# soap-disp-20210413.net
KiCad netlist of a schematic drawn in EasyEDA
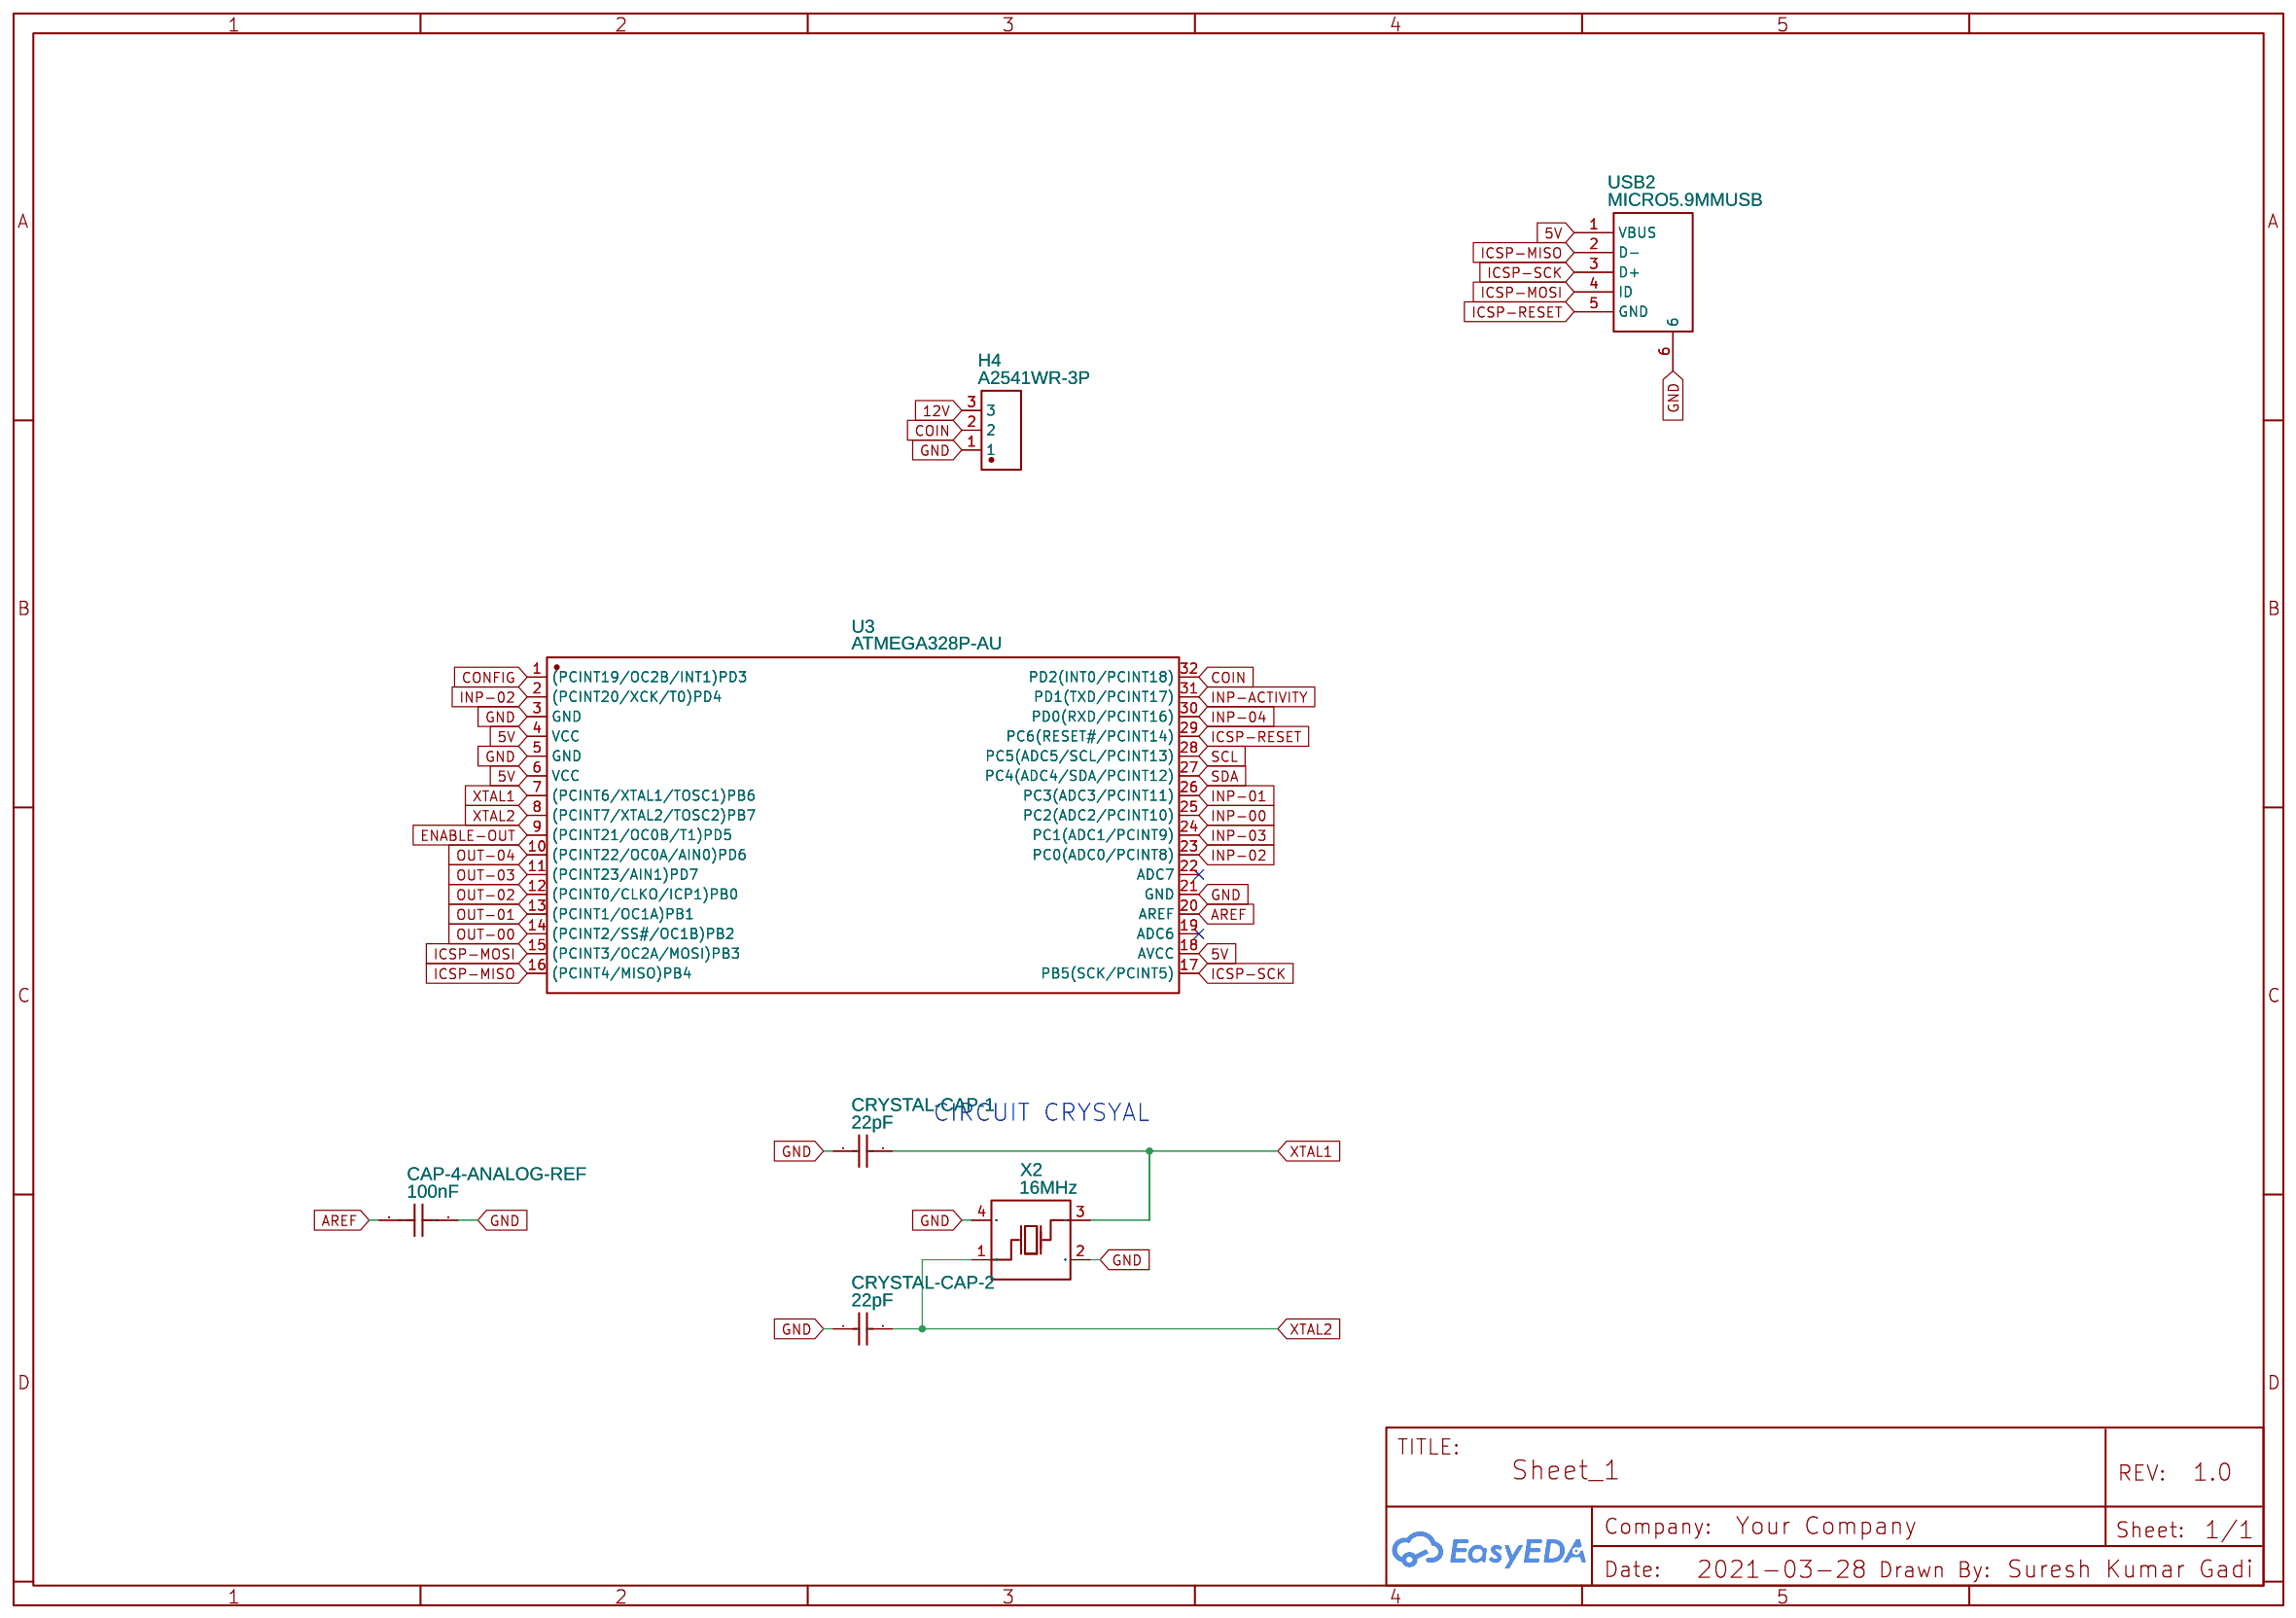
[diagram p0: Computer]
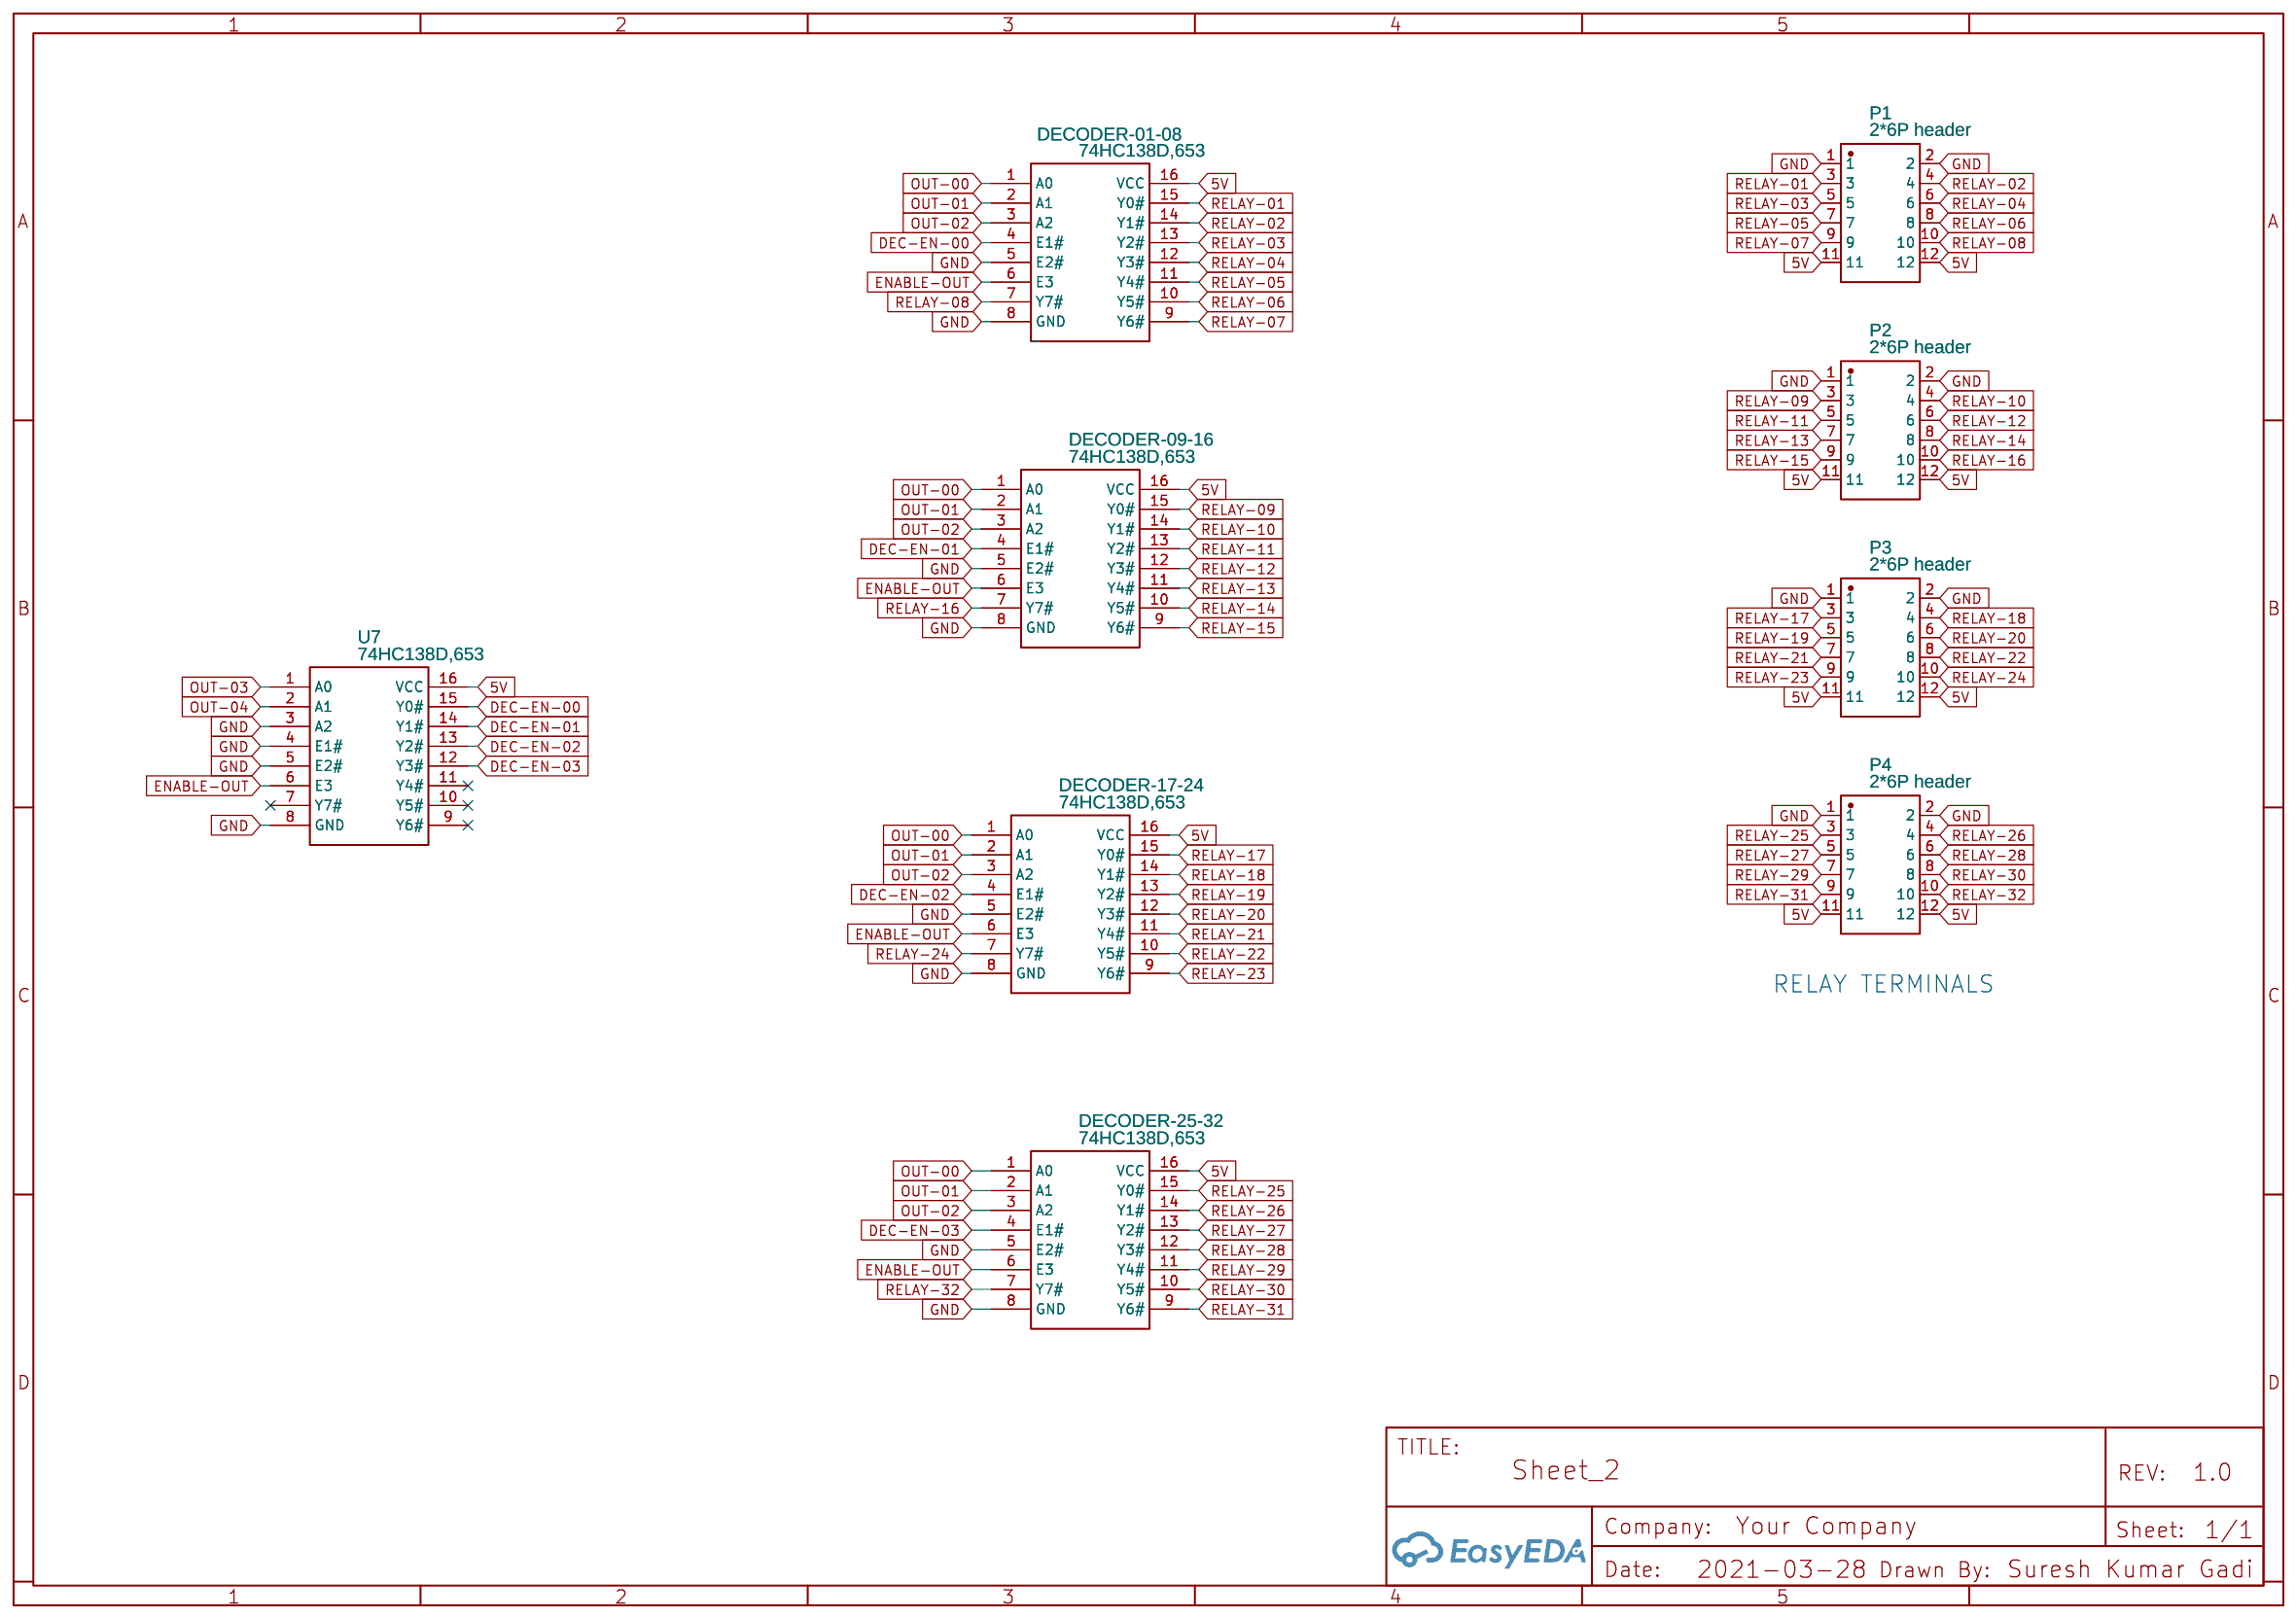
[diagram p1: Relays]
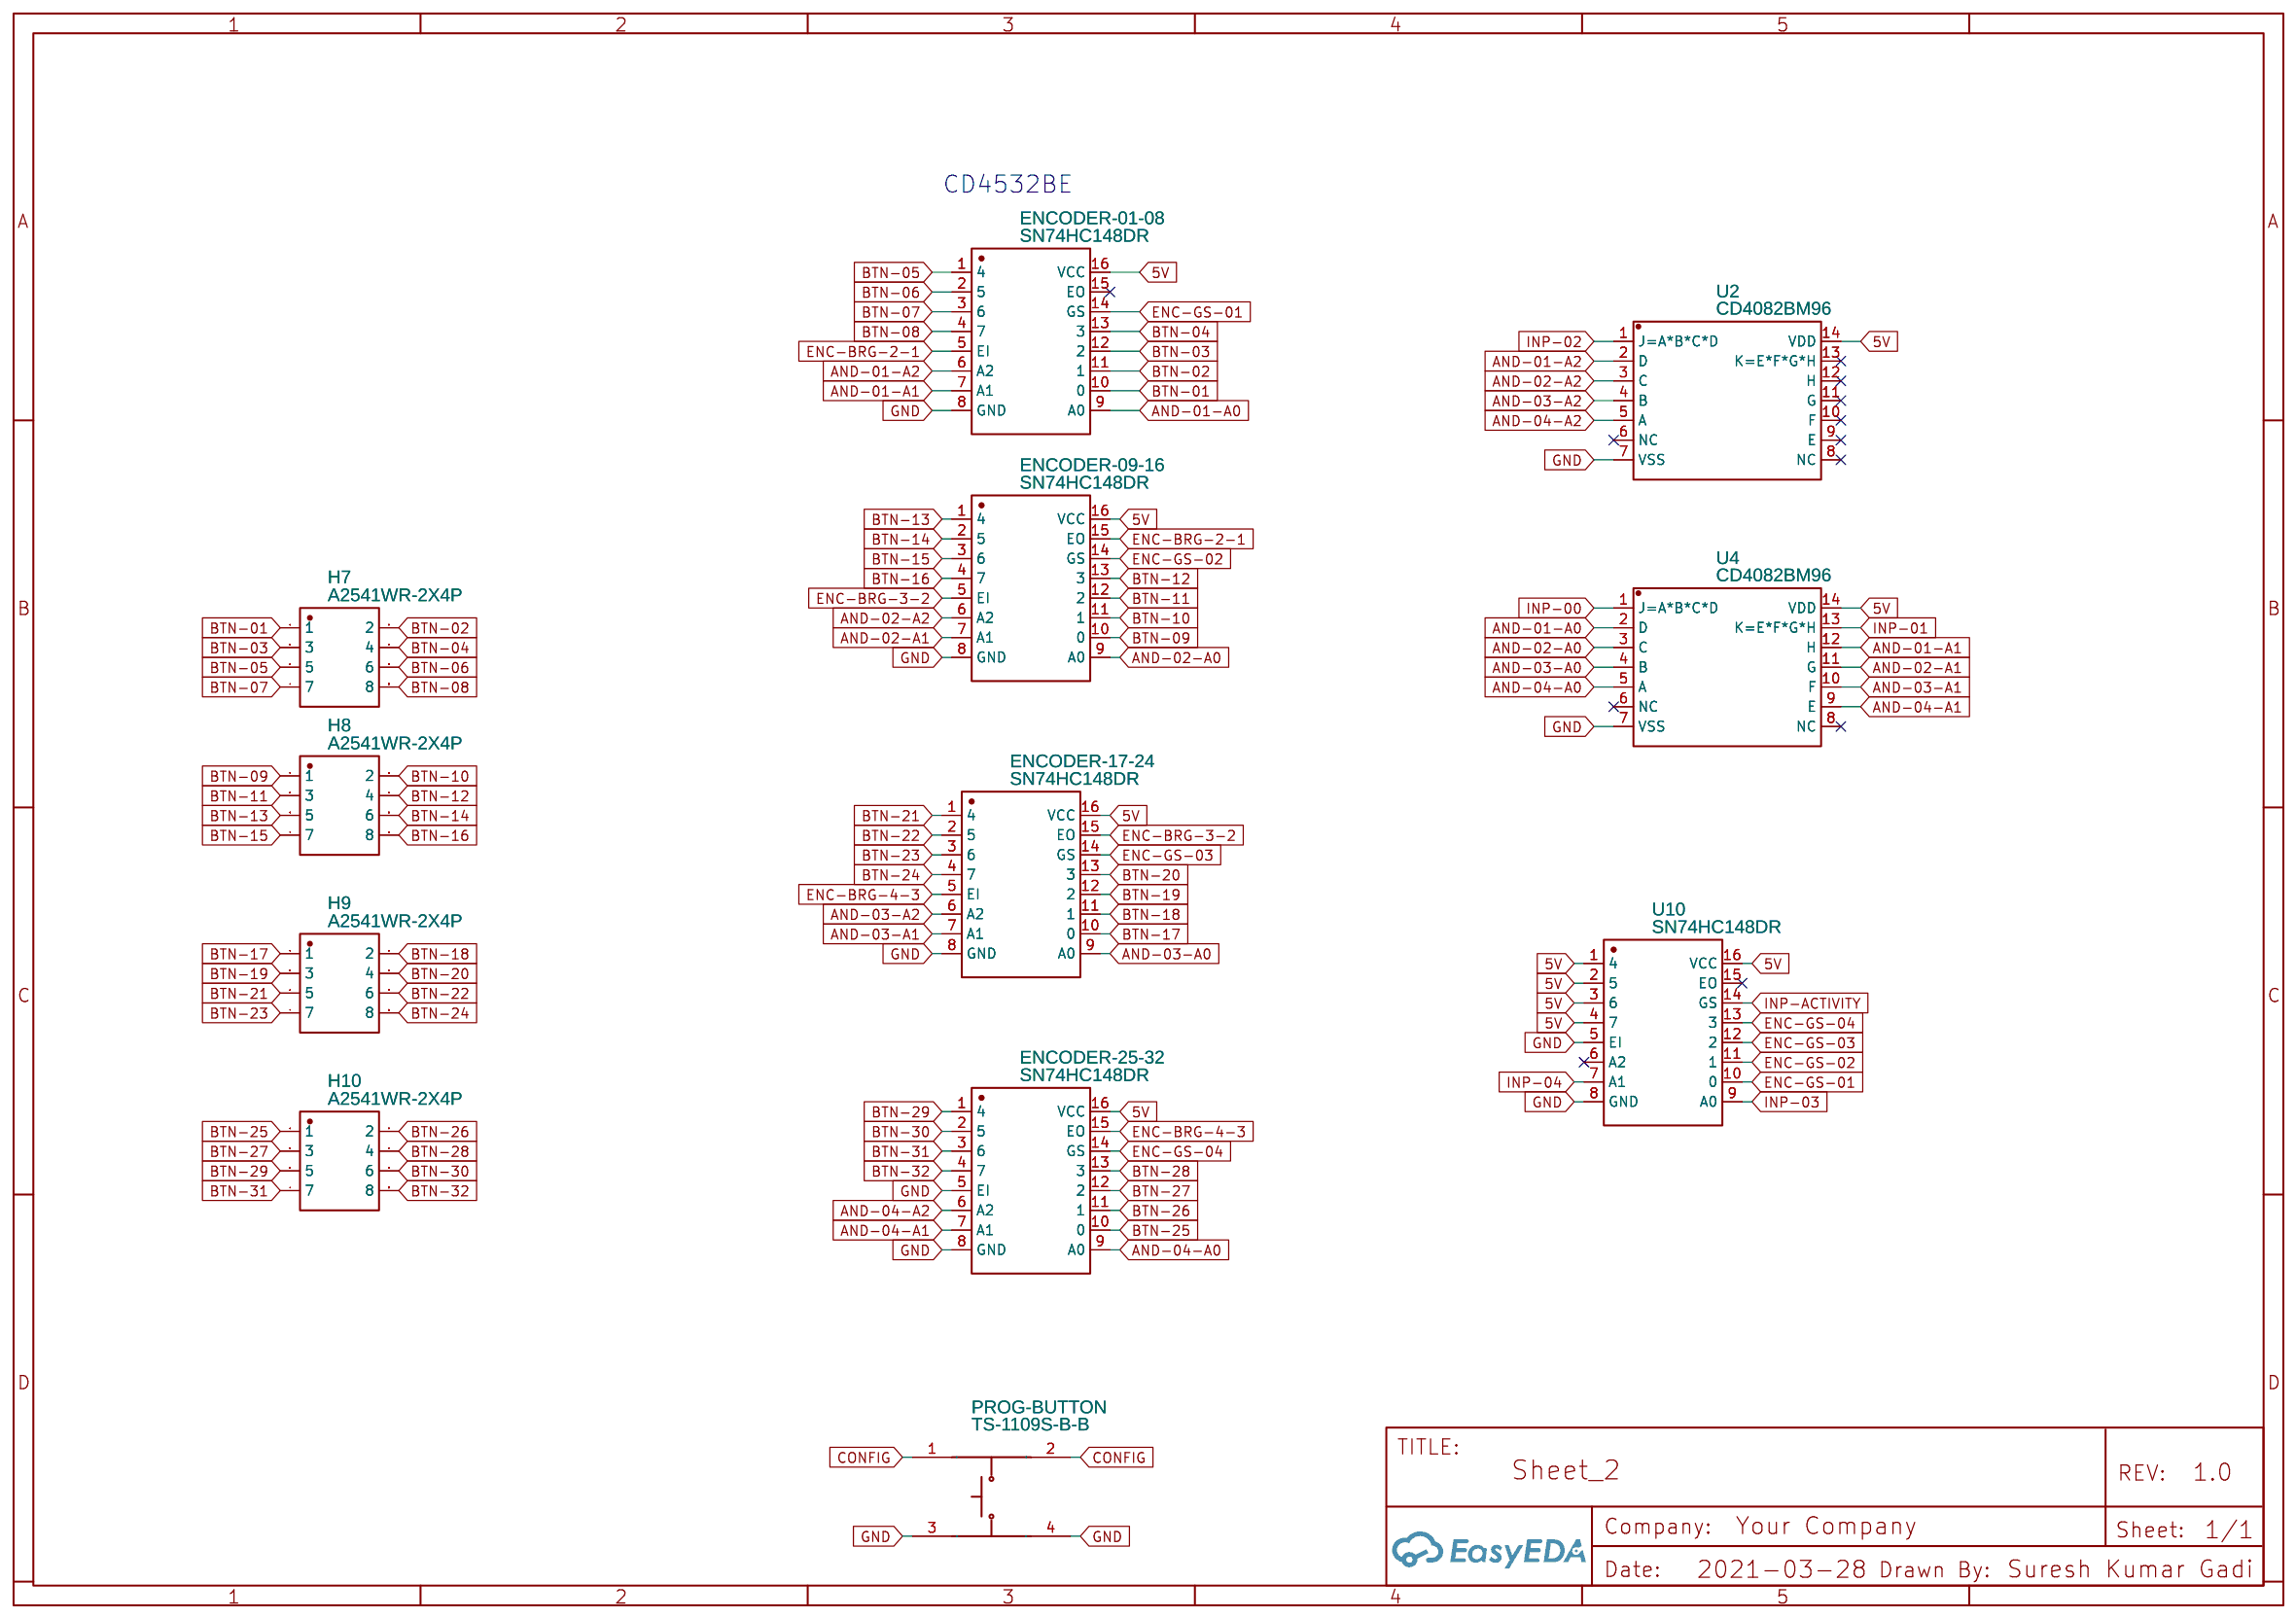
[diagram p2: Buttons]
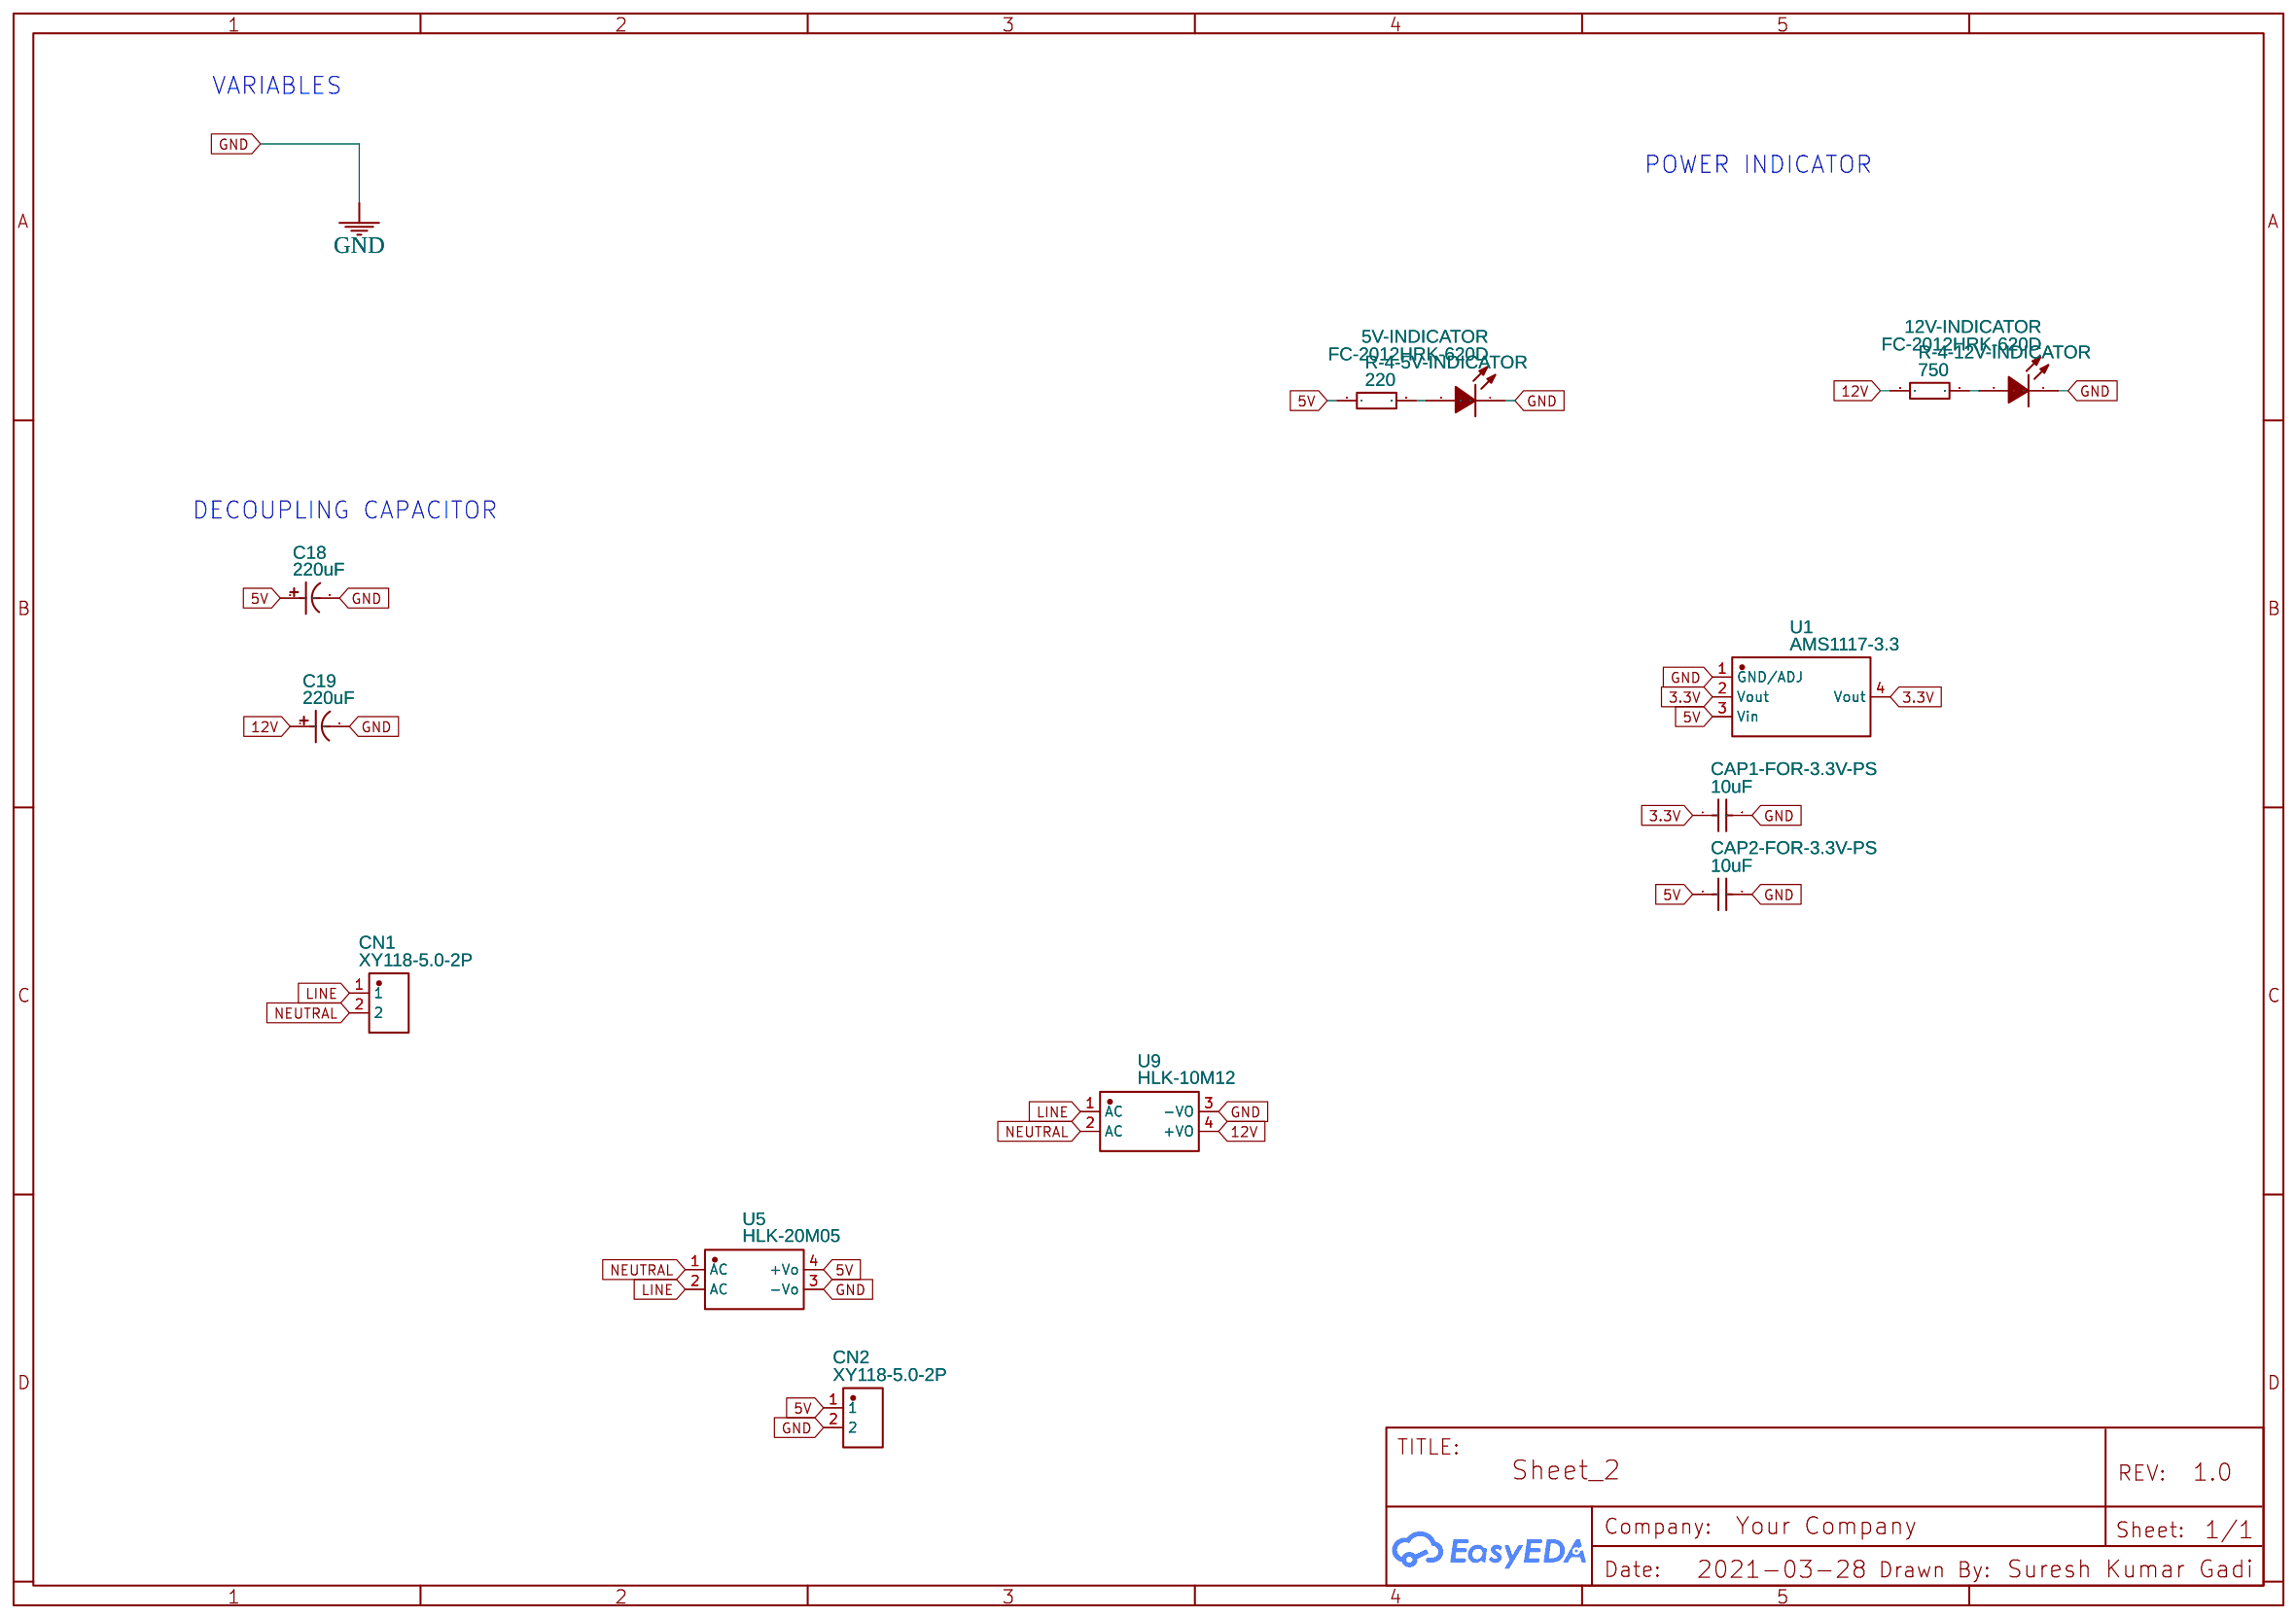
[diagram p3: Power]
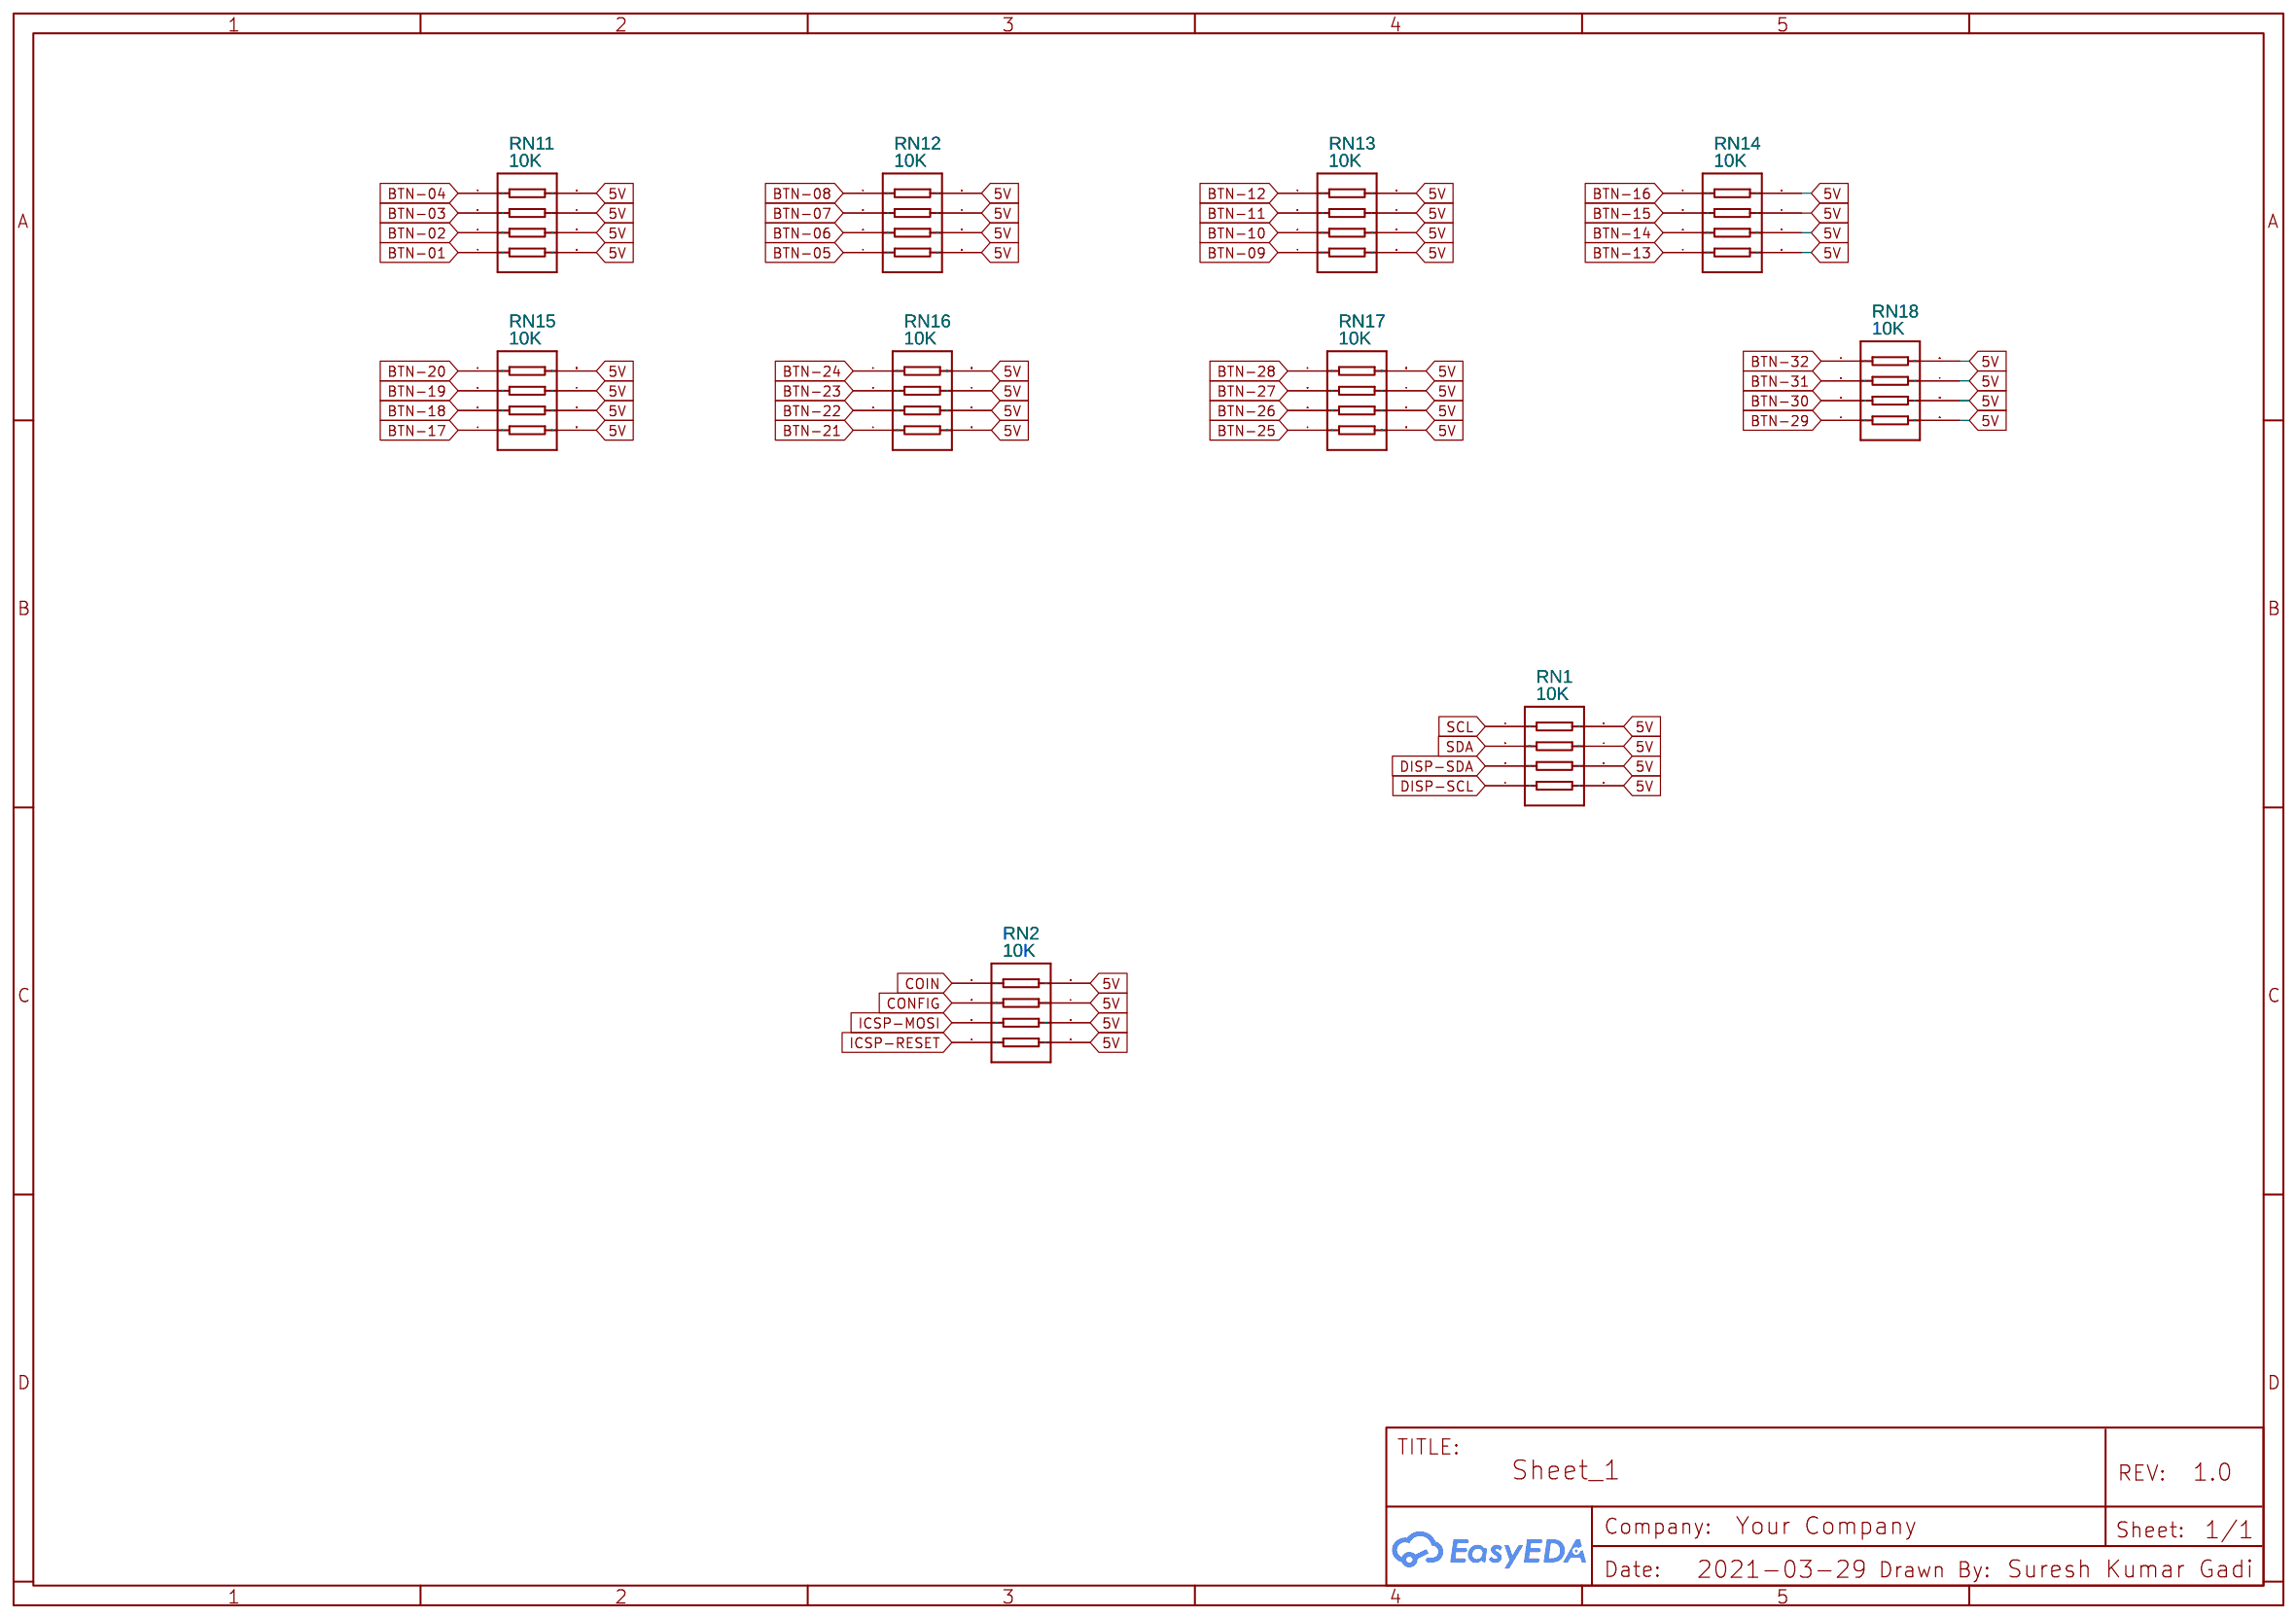
[diagram p4: Pull up-down]
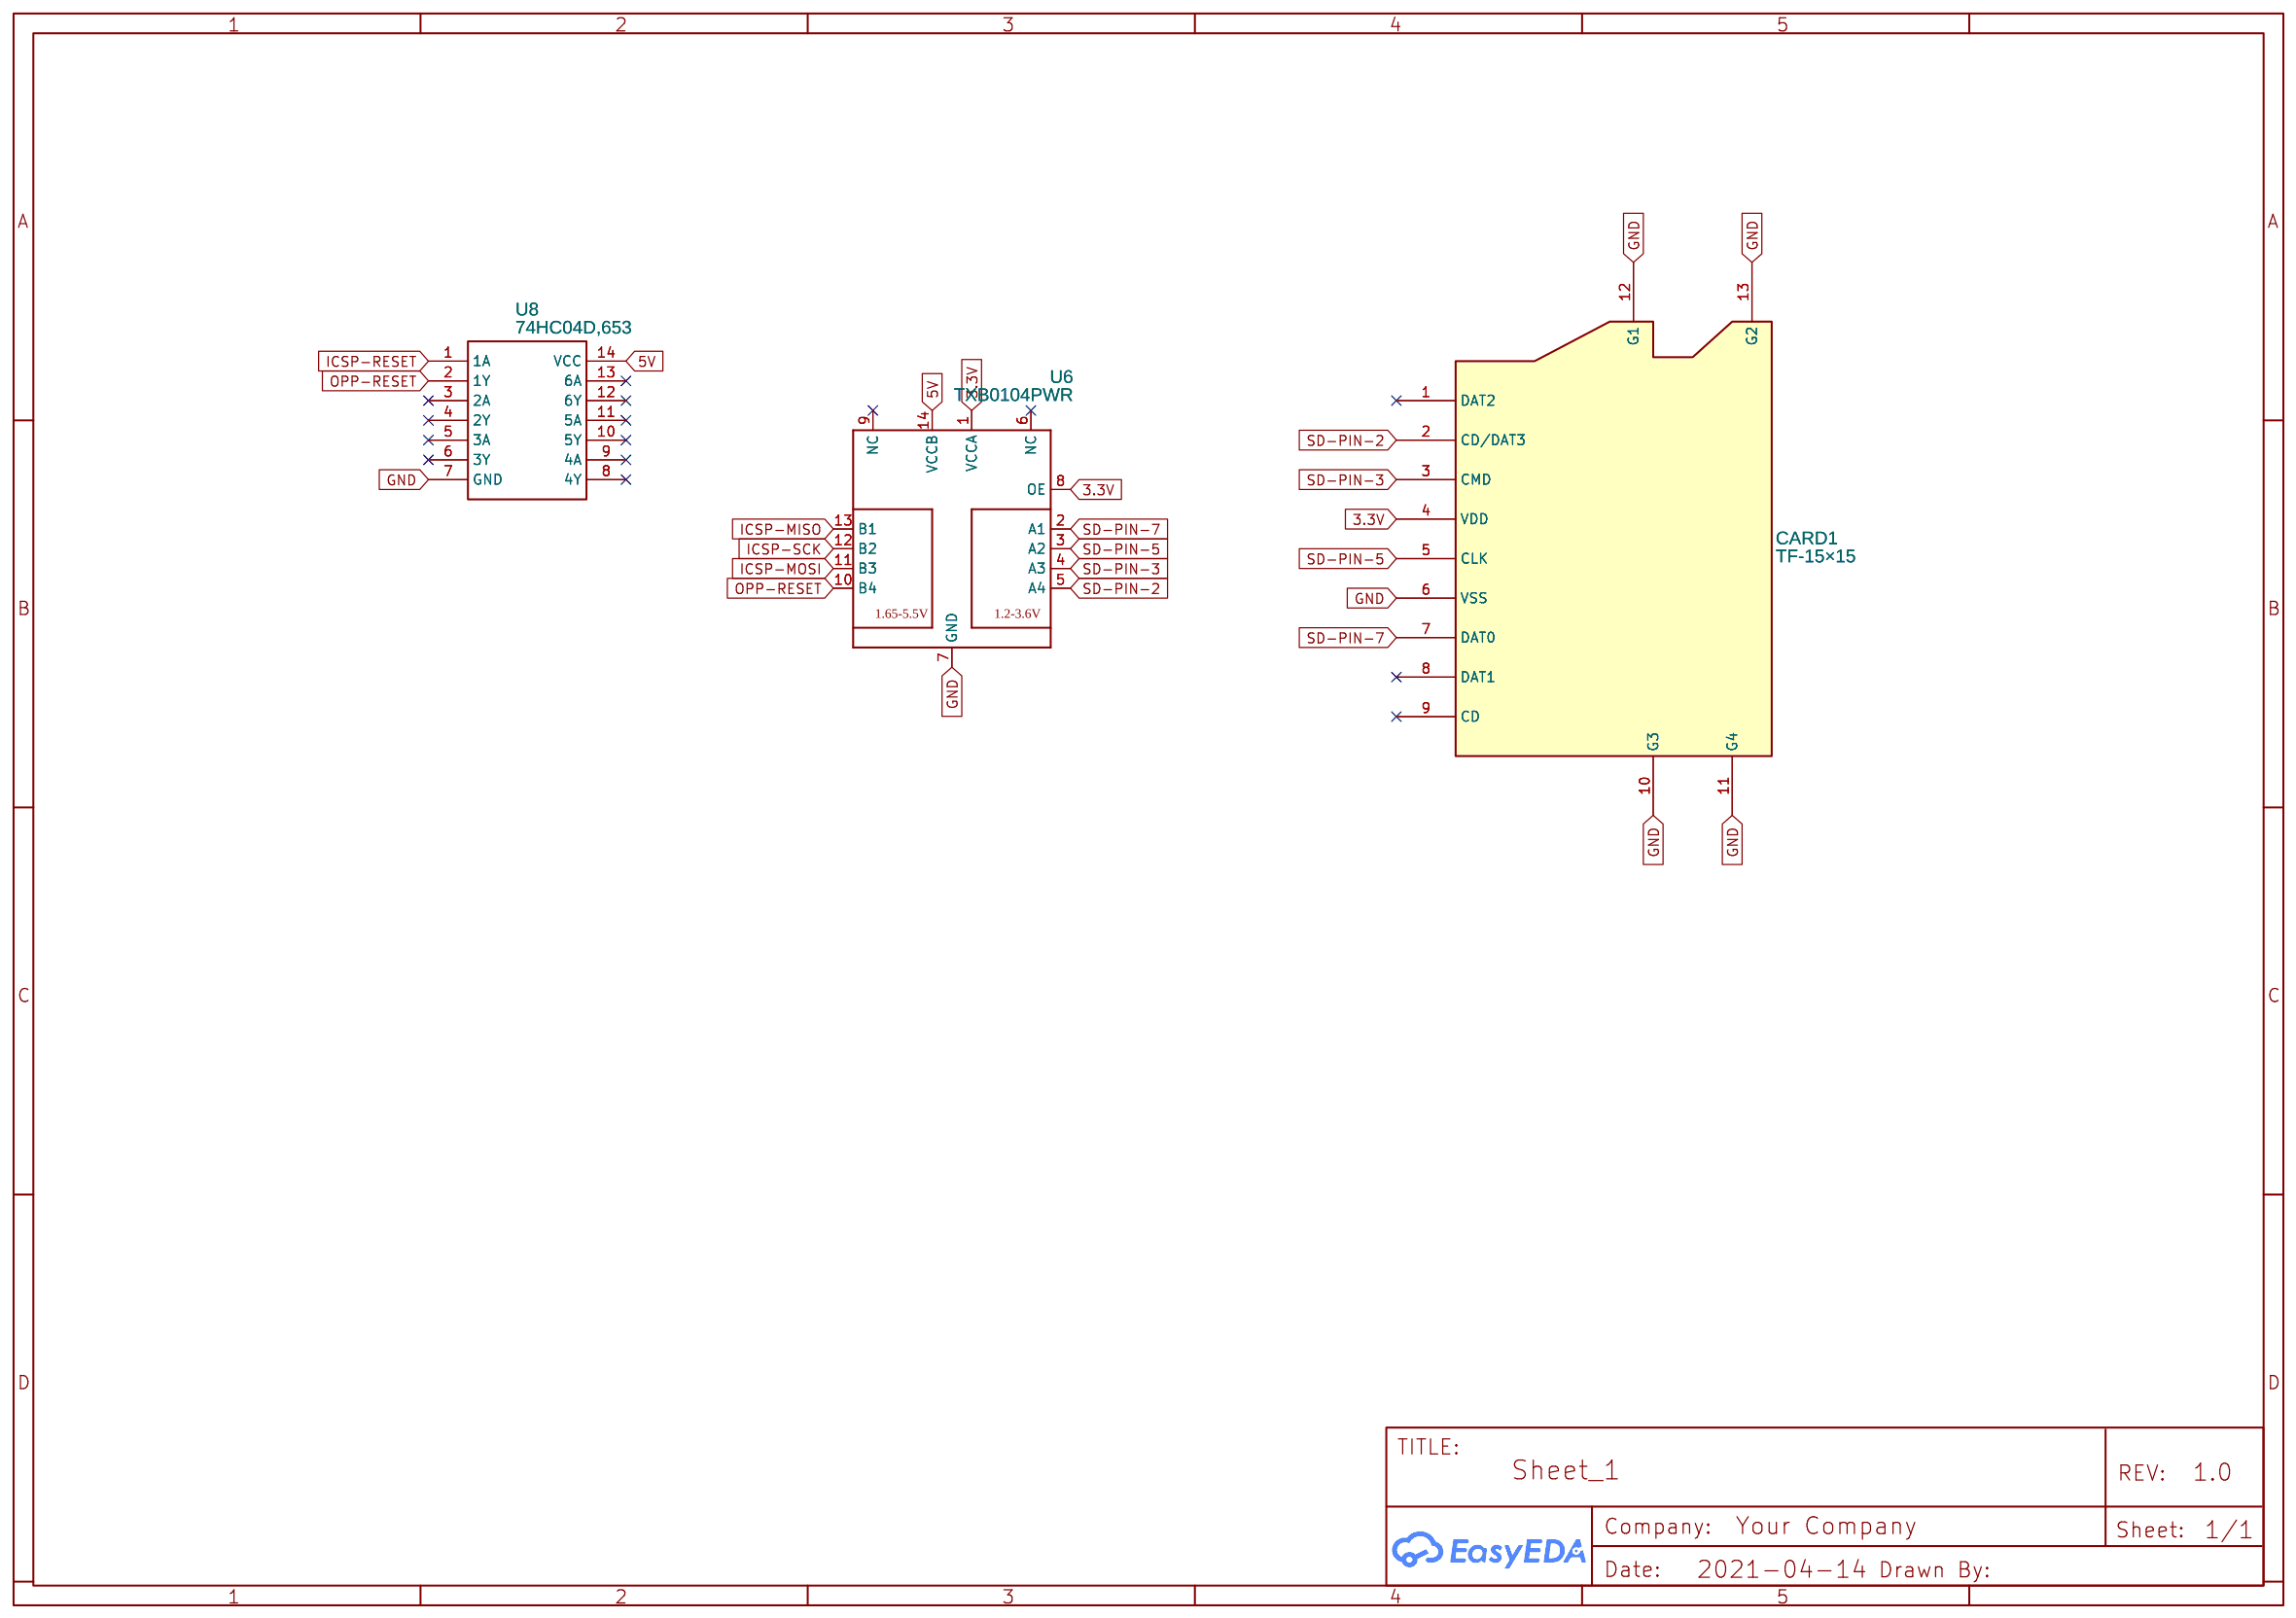
[diagram p5: SD Card]
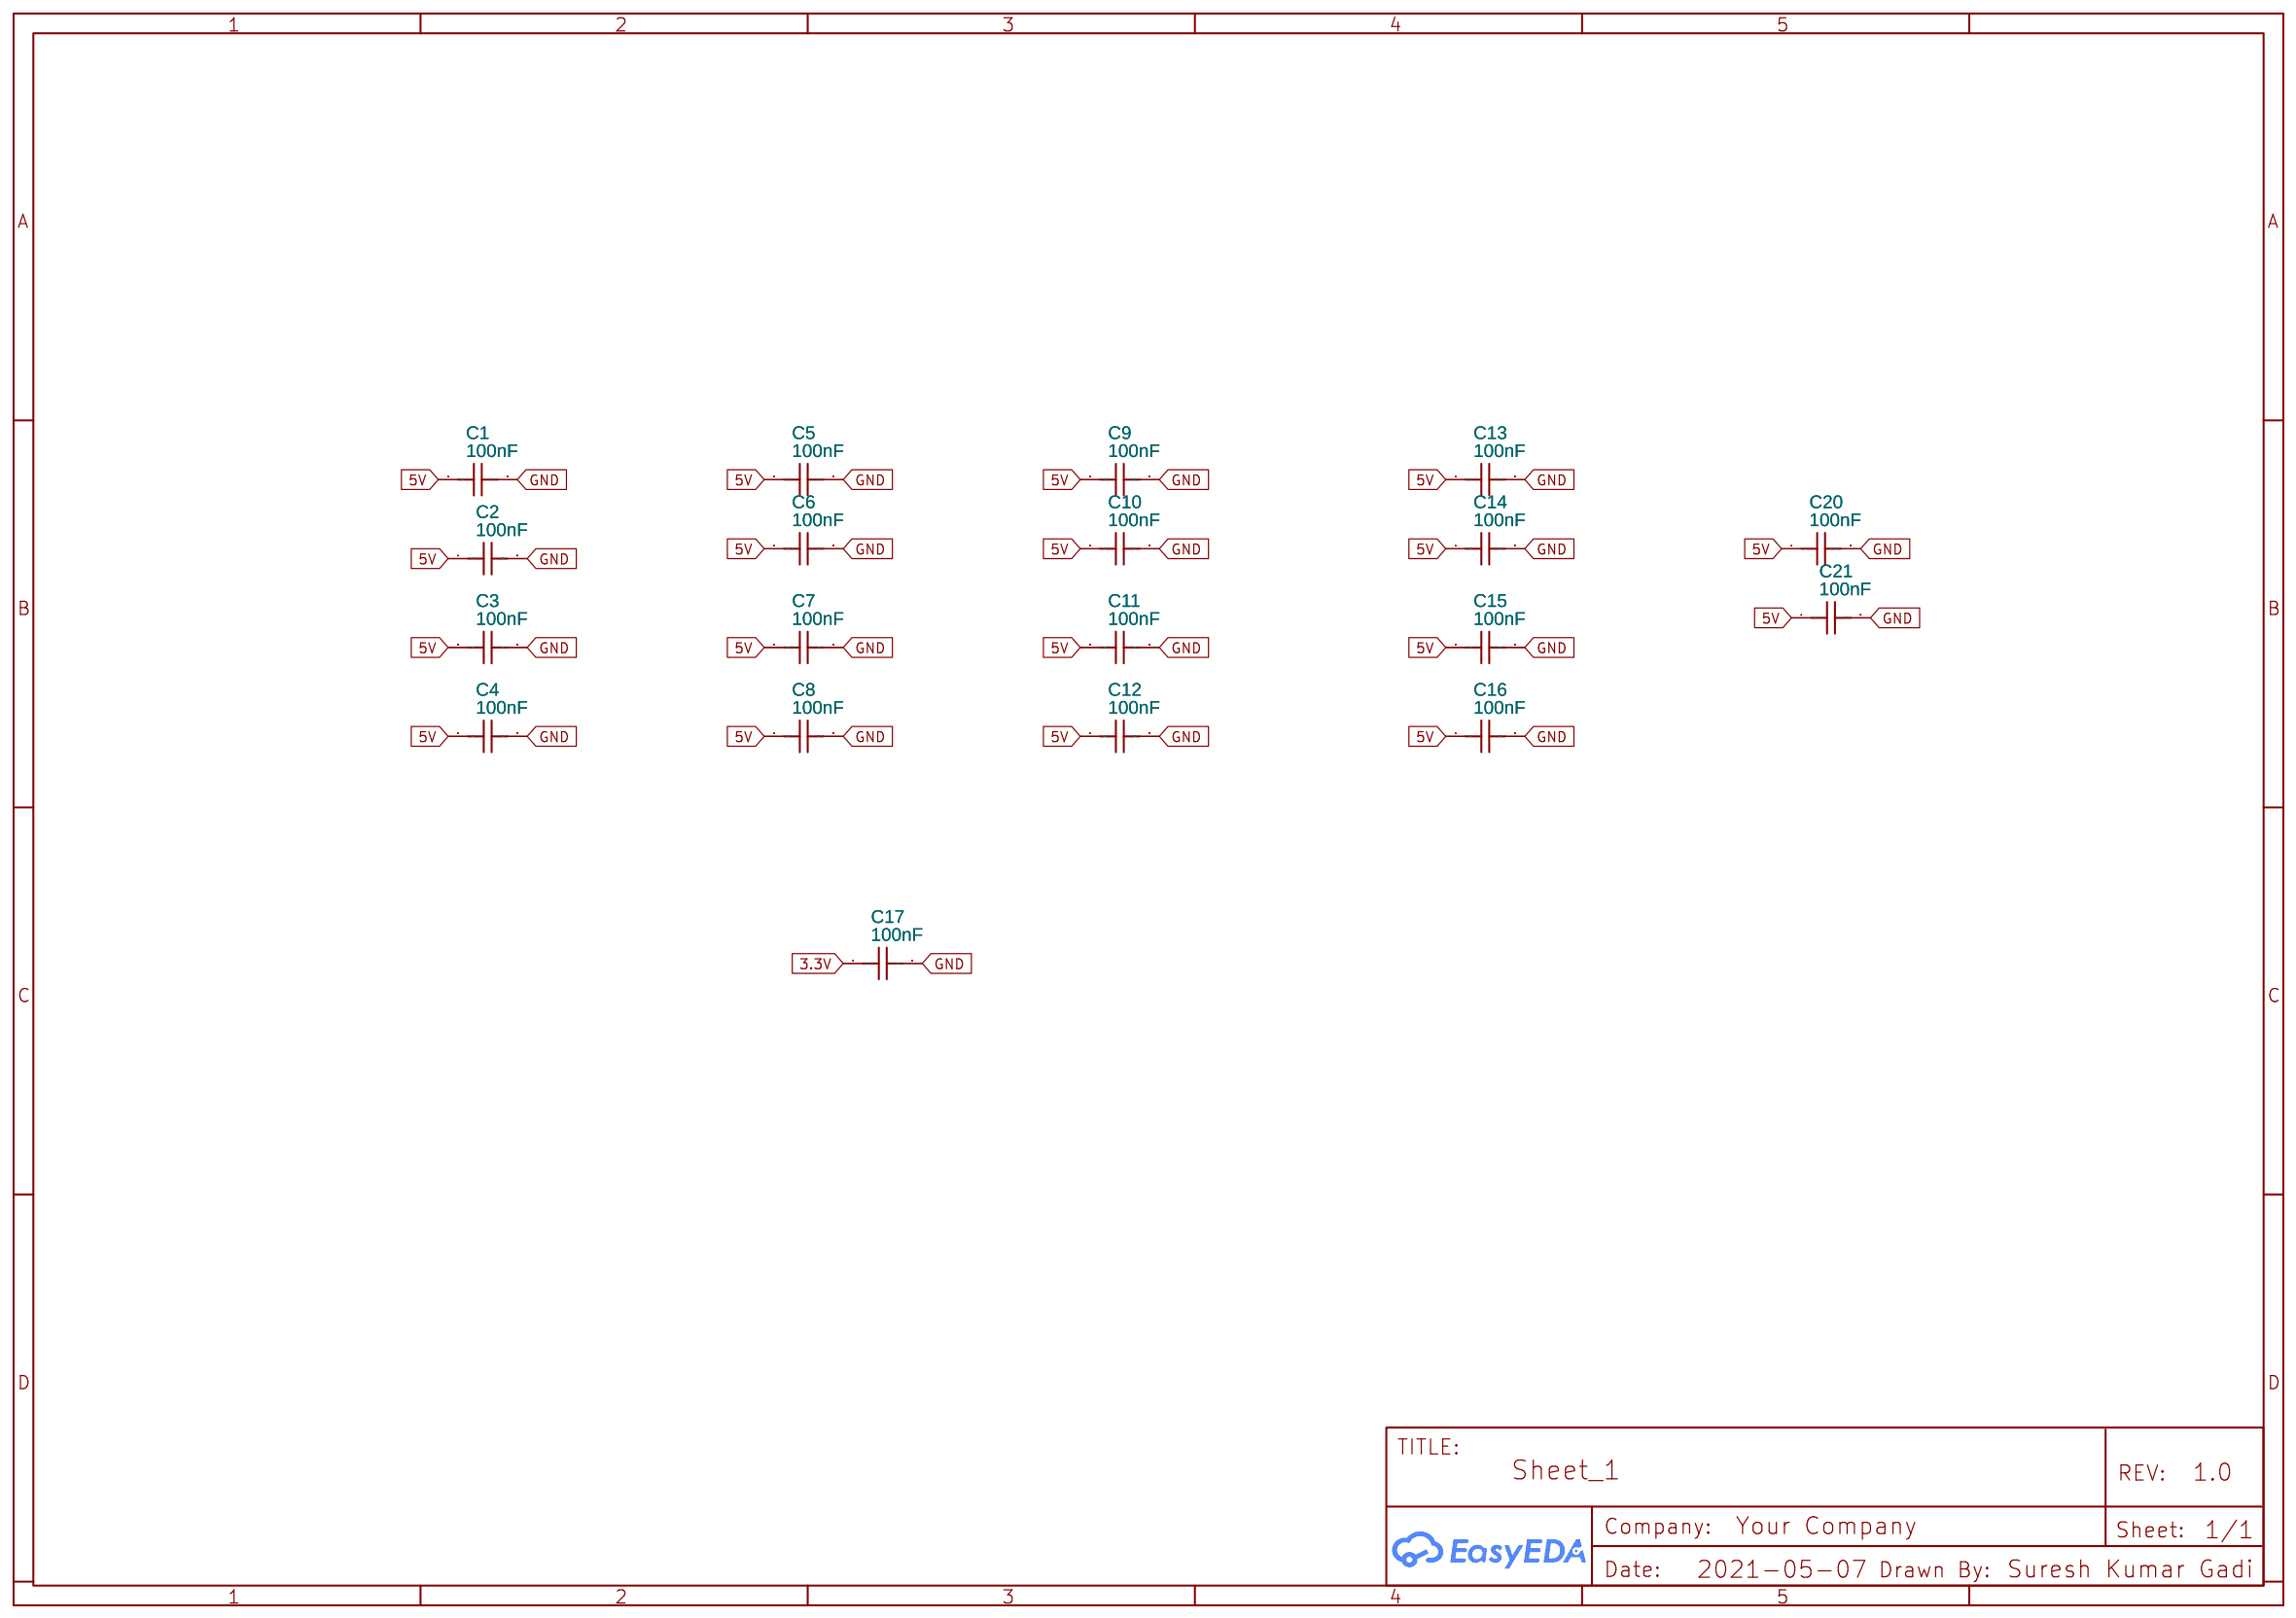
[diagram p6: Capacitor]
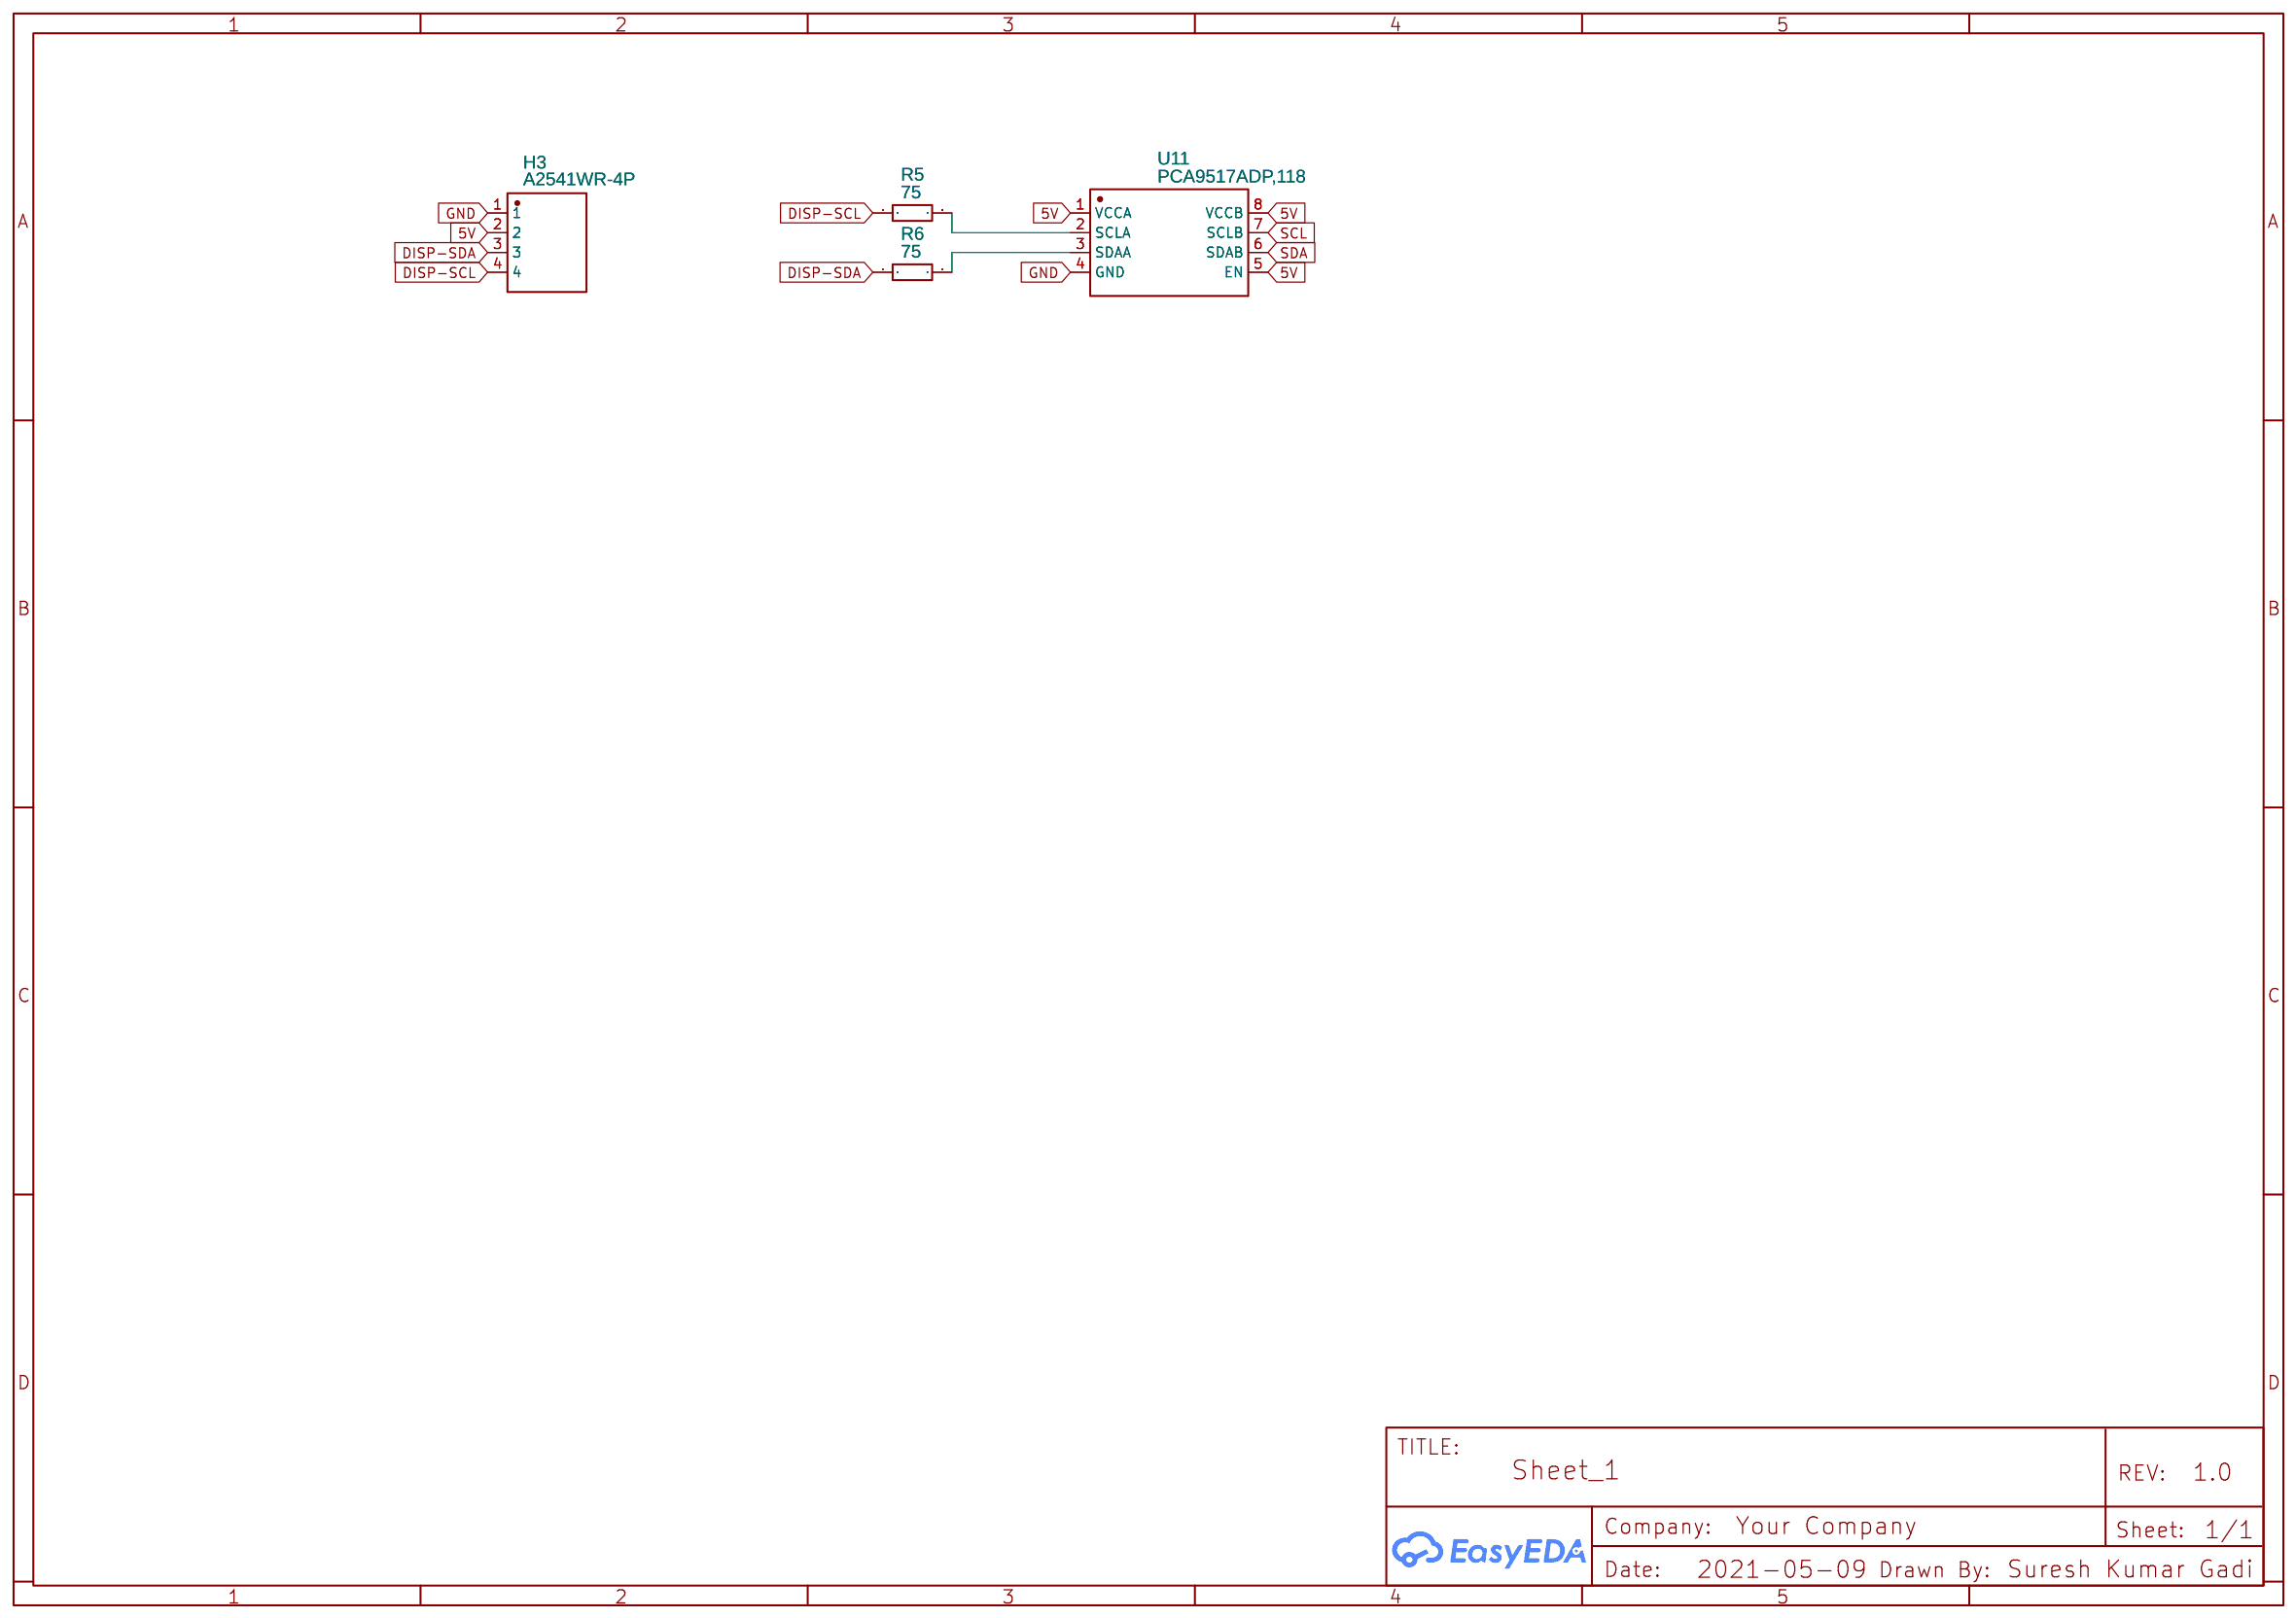
[diagram p7: Display]
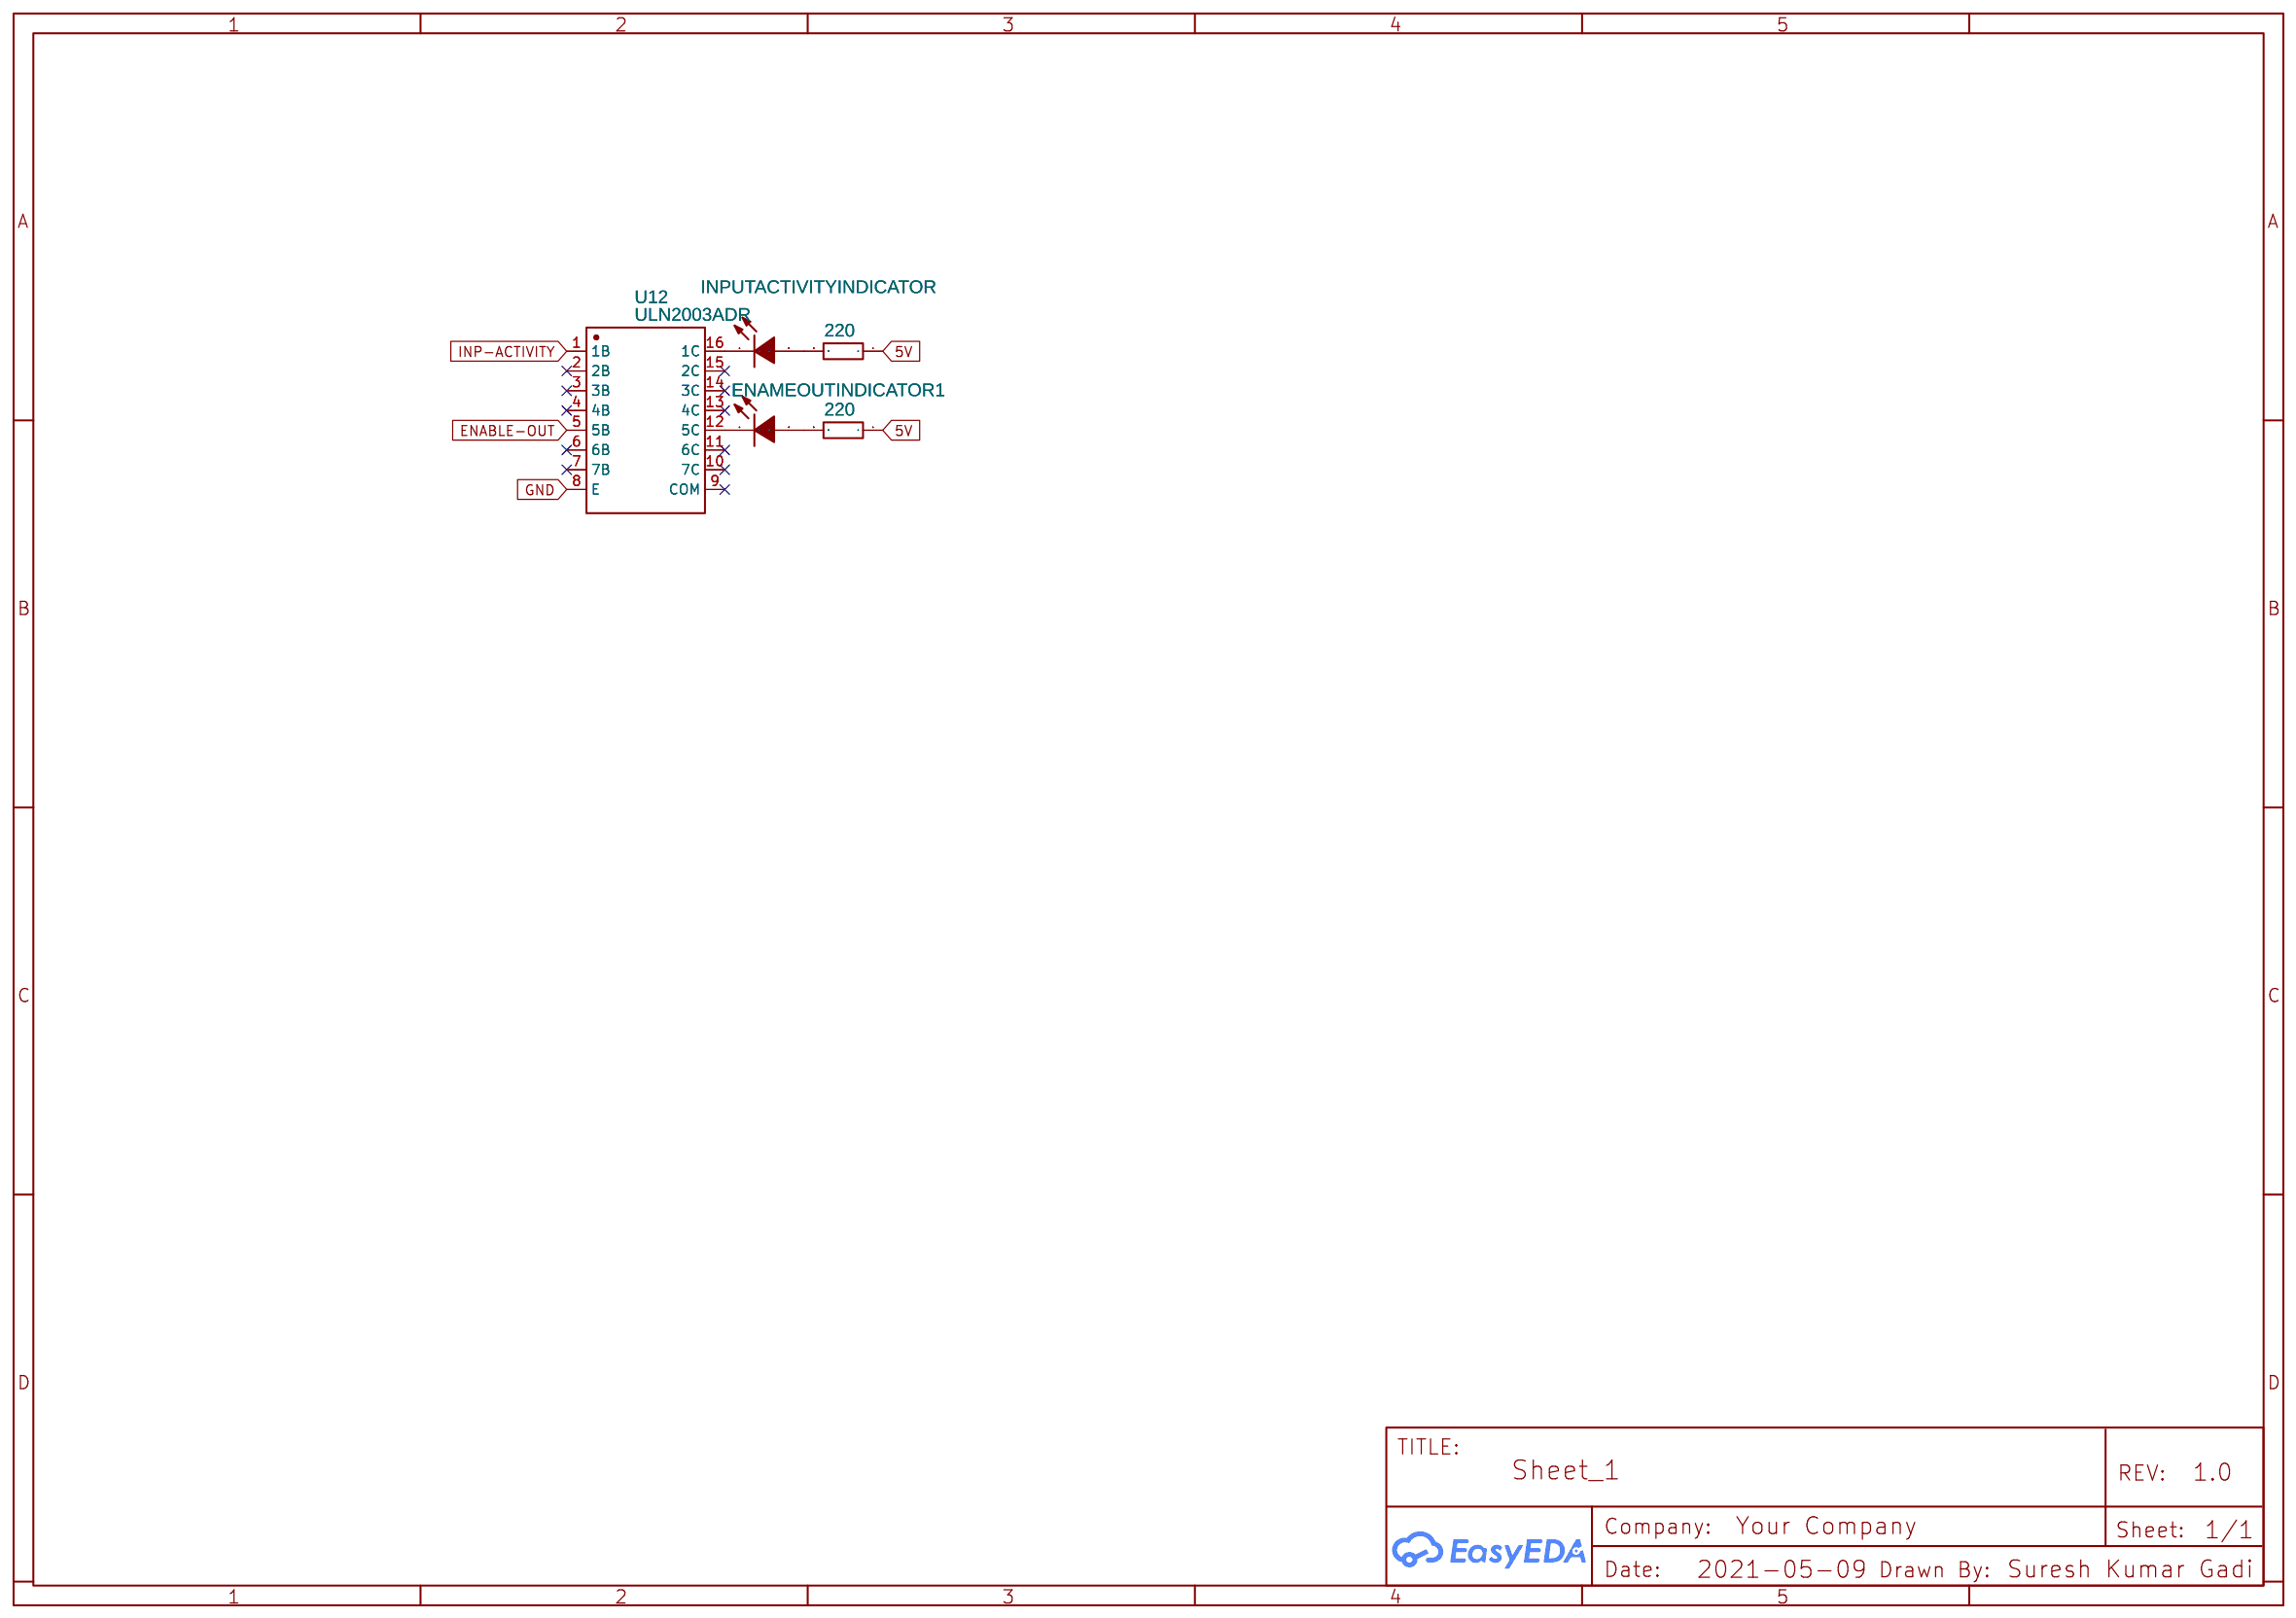
[diagram p8: LEDs]

(export (version "E")
  (design (tool "Eeschema 10.0.6"))
  (components
    (comp (ref "CAP-4-ANALOG-REF")
      (value "100nF")
      (fields
        (field (name "BOM_Manufacturer Part") "CC0603KRX7R9BB104")
        (field (name "BOM_Supplier Part") "C14663")
      )
      (libsource (lib "") (part "CC0603KRX7R9BB104"))
    )
    (comp (ref "CRYSTAL-CAP-1")
      (value "22pF")
      (fields
        (field (name "BOM_Manufacturer Part") "CL21C220JBANNNC")
        (field (name "BOM_Supplier Part") "C1804")
      )
      (libsource (lib "") (part "CL21C220JBANNNC"))
    )
    (comp (ref "CRYSTAL-CAP-2")
      (value "22pF")
      (fields
        (field (name "BOM_Manufacturer Part") "CL21C220JBANNNC")
        (field (name "BOM_Supplier Part") "C1804")
      )
      (libsource (lib "") (part "CL21C220JBANNNC"))
    )
    (comp (ref "H4")
      (value "A2541WR-3P")
      (fields (field (name "BOM_Supplier Part") "C225489"))
      (libsource (lib "") (part "A2541WR-3P"))
    )
    (comp (ref "U3")
      (value "ATMEGA328P-AU")
      (fields (field (name "BOM_Supplier Part") "C14877"))
      (libsource (lib "") (part "ATMEGA328P-AU"))
    )
    (comp (ref "USB2")
      (value "MICRO5.9MMUSB")
      (fields
        (field (name "BOM_Manufacturer Part") "MICRO5.9mmusb")
        (field (name "BOM_Supplier Part") "C393940")
      )
      (libsource (lib "") (part "MICRO5.9MMUSB"))
    )
    (comp (ref "X2")
      (value "16MHz")
      (fields
        (field (name "BOM_Manufacturer Part") "X322516MLB4SI")
        (field (name "BOM_Supplier Part") "C13738")
      )
      (libsource (lib "") (part "X322516MLB4SI"))
    )
    (comp (ref "DECODER-01-08")
      (value "74HC138D,653")
      (fields (field (name "BOM_Supplier Part") "C5602"))
      (libsource (lib "") (part "74HC138D,653_4"))
    )
    (comp (ref "DECODER-09-16")
      (value "74HC138D,653")
      (fields (field (name "BOM_Supplier Part") "C5602"))
      (libsource (lib "") (part "74HC138D,653"))
    )
    (comp (ref "DECODER-17-24")
      (value "74HC138D,653")
      (fields (field (name "BOM_Supplier Part") "C5602"))
      (libsource (lib "") (part "74HC138D,653_1"))
    )
    (comp (ref "DECODER-25-32")
      (value "74HC138D,653")
      (fields (field (name "BOM_Supplier Part") "C5602"))
      (libsource (lib "") (part "74HC138D,653_2"))
    )
    (comp (ref "P1")
      (value "2*6P header")
      (fields (field (name "BOM_Supplier Part") "C60565"))
      (libsource (lib "") (part "2*6P header"))
    )
    (comp (ref "P2")
      (value "2*6P header")
      (fields (field (name "BOM_Supplier Part") "C60565"))
      (libsource (lib "") (part "2*6P header"))
    )
    (comp (ref "P3")
      (value "2*6P header")
      (fields (field (name "BOM_Supplier Part") "C60565"))
      (libsource (lib "") (part "2*6P header"))
    )
    (comp (ref "P4")
      (value "2*6P header")
      (fields (field (name "BOM_Supplier Part") "C60565"))
      (libsource (lib "") (part "2*6P header"))
    )
    (comp (ref "U7")
      (value "74HC138D,653")
      (fields (field (name "BOM_Supplier Part") "C5602"))
      (libsource (lib "") (part "74HC138D,653_3"))
    )
    (comp (ref "ENCODER-01-08")
      (value "SN74HC148DR")
      (fields (field (name "BOM_Supplier Part") "C6819"))
      (libsource (lib "") (part "SN74HC148DR_3"))
    )
    (comp (ref "ENCODER-09-16")
      (value "SN74HC148DR")
      (fields (field (name "BOM_Supplier Part") "C6819"))
      (libsource (lib "") (part "SN74HC148DR"))
    )
    (comp (ref "ENCODER-17-24")
      (value "SN74HC148DR")
      (fields (field (name "BOM_Supplier Part") "C6819"))
      (libsource (lib "") (part "SN74HC148DR_4"))
    )
    (comp (ref "ENCODER-25-32")
      (value "SN74HC148DR")
      (fields (field (name "BOM_Supplier Part") "C6819"))
      (libsource (lib "") (part "SN74HC148DR_1"))
    )
    (comp (ref "H7")
      (value "A2541WR-2X4P")
      (fields
        (field (name "BOM_Manufacturer Part") "A2541WR-2x4P")
        (field (name "BOM_Supplier Part") "C239335")
      )
      (libsource (lib "") (part "A2541WR-2X4P"))
    )
    (comp (ref "H8")
      (value "A2541WR-2X4P")
      (fields
        (field (name "BOM_Manufacturer Part") "A2541WR-2x4P")
        (field (name "BOM_Supplier Part") "C239335")
      )
      (libsource (lib "") (part "A2541WR-2X4P"))
    )
    (comp (ref "H9")
      (value "A2541WR-2X4P")
      (fields
        (field (name "BOM_Manufacturer Part") "A2541WR-2x4P")
        (field (name "BOM_Supplier Part") "C239335")
      )
      (libsource (lib "") (part "A2541WR-2X4P"))
    )
    (comp (ref "H10")
      (value "A2541WR-2X4P")
      (fields
        (field (name "BOM_Manufacturer Part") "A2541WR-2x4P")
        (field (name "BOM_Supplier Part") "C239335")
      )
      (libsource (lib "") (part "A2541WR-2X4P"))
    )
    (comp (ref "PROG-BUTTON")
      (value "TS-1109S-B-B")
      (fields (field (name "BOM_Supplier Part") "C480315"))
      (libsource (lib "") (part "TS-1109S-B-B"))
    )
    (comp (ref "U2")
      (value "CD4082BM96")
      (fields (field (name "BOM_Supplier Part") "C193801"))
      (libsource (lib "") (part "CD4082BM96"))
    )
    (comp (ref "U4")
      (value "CD4082BM96")
      (fields (field (name "BOM_Supplier Part") "C193801"))
      (libsource (lib "") (part "CD4082BM96"))
    )
    (comp (ref "U10")
      (value "SN74HC148DR")
      (fields (field (name "BOM_Supplier Part") "C6819"))
      (libsource (lib "") (part "SN74HC148DR_2"))
    )
    (comp (ref "5V-INDICATOR")
      (value "FC-2012HRK-620D")
      (fields (field (name "BOM_Supplier Part") "C84256"))
      (libsource (lib "") (part "FC-2012HRK-620D"))
    )
    (comp (ref "12V-INDICATOR")
      (value "FC-2012HRK-620D")
      (fields (field (name "BOM_Supplier Part") "C84256"))
      (libsource (lib "") (part "FC-2012HRK-620D_1"))
    )
    (comp (ref "C18")
      (value "220uF")
      (fields
        (field (name "BOM_Manufacturer Part") "RVT1H221M1010")
        (field (name "BOM_Supplier Part") "C3358")
      )
      (libsource (lib "") (part "RVT1H221M1010-C3358"))
    )
    (comp (ref "C19")
      (value "220uF")
      (fields
        (field (name "BOM_Manufacturer Part") "RVT1H221M1010")
        (field (name "BOM_Supplier Part") "C3358")
      )
      (libsource (lib "") (part "RVT1H221M1010-C3358"))
    )
    (comp (ref "CAP1-FOR-3.3V-PS")
      (value "10uF")
      (fields
        (field (name "BOM_Manufacturer Part") "CL21A106KAYNNNE")
        (field (name "BOM_Supplier Part") "C15850")
      )
      (libsource (lib "") (part "CL21A106KAYNNNE_1"))
    )
    (comp (ref "CAP2-FOR-3.3V-PS")
      (value "10uF")
      (fields
        (field (name "BOM_Manufacturer Part") "CL21A106KAYNNNE")
        (field (name "BOM_Supplier Part") "C15850")
      )
      (libsource (lib "") (part "CL21A106KAYNNNE"))
    )
    (comp (ref "CN1")
      (value "XY118-5.0-2P")
      (fields (field (name "BOM_Supplier Part") "C784922"))
      (libsource (lib "") (part "XY118-5.0-2P"))
    )
    (comp (ref "CN2")
      (value "XY118-5.0-2P")
      (fields (field (name "BOM_Supplier Part") "C784922"))
      (libsource (lib "") (part "XY118-5.0-2P"))
    )
    (comp (ref "R-4-5V-INDICATOR")
      (value "220")
      (fields
        (field (name "BOM_Manufacturer Part") "0805W8F2200T5E")
        (field (name "BOM_Supplier Part") "C17557")
      )
      (libsource (lib "") (part "0805W8F2200T5E"))
    )
    (comp (ref "R-4-12V-INDICATOR")
      (value "750")
      (fields
        (field (name "BOM_Manufacturer Part") "1206W4F7500T5E")
        (field (name "BOM_Supplier Part") "C17985")
      )
      (libsource (lib "") (part "1206W4F7500T5E"))
    )
    (comp (ref "U1")
      (value "AMS1117-3.3")
      (fields (field (name "BOM_Supplier Part") "C6186"))
      (libsource (lib "") (part "AMS1117-3.3"))
    )
    (comp (ref "U5")
      (value "HLK-20M05")
      (fields (field (name "BOM_Supplier Part") "C465406"))
      (libsource (lib "") (part "HLK-20M05"))
    )
    (comp (ref "U9")
      (value "HLK-10M12")
      (fields (field (name "BOM_Supplier Part") "C403746"))
      (libsource (lib "") (part "HLK-10M12"))
    )
    (comp (ref "RN1")
      (value "10K")
      (fields
        (field (name "BOM_Manufacturer Part") "4D03WGJ0103T5E")
        (field (name "BOM_Supplier Part") "C29718")
      )
      (libsource (lib "") (part "4D03WGJ0103T5E"))
    )
    (comp (ref "RN2")
      (value "10K")
      (fields
        (field (name "BOM_Manufacturer Part") "4D03WGJ0103T5E")
        (field (name "BOM_Supplier Part") "C29718")
      )
      (libsource (lib "") (part "4D03WGJ0103T5E"))
    )
    (comp (ref "RN11")
      (value "10K")
      (fields
        (field (name "BOM_Manufacturer Part") "4D03WGJ0103T5E")
        (field (name "BOM_Supplier Part") "C29718")
      )
      (libsource (lib "") (part "4D03WGJ0103T5E"))
    )
    (comp (ref "RN12")
      (value "10K")
      (fields
        (field (name "BOM_Manufacturer Part") "4D03WGJ0103T5E")
        (field (name "BOM_Supplier Part") "C29718")
      )
      (libsource (lib "") (part "4D03WGJ0103T5E"))
    )
    (comp (ref "RN13")
      (value "10K")
      (fields
        (field (name "BOM_Manufacturer Part") "4D03WGJ0103T5E")
        (field (name "BOM_Supplier Part") "C29718")
      )
      (libsource (lib "") (part "4D03WGJ0103T5E"))
    )
    (comp (ref "RN14")
      (value "10K")
      (fields
        (field (name "BOM_Manufacturer Part") "4D03WGJ0103T5E")
        (field (name "BOM_Supplier Part") "C29718")
      )
      (libsource (lib "") (part "4D03WGJ0103T5E"))
    )
    (comp (ref "RN15")
      (value "10K")
      (fields
        (field (name "BOM_Manufacturer Part") "4D03WGJ0103T5E")
        (field (name "BOM_Supplier Part") "C29718")
      )
      (libsource (lib "") (part "4D03WGJ0103T5E"))
    )
    (comp (ref "RN16")
      (value "10K")
      (fields
        (field (name "BOM_Manufacturer Part") "4D03WGJ0103T5E")
        (field (name "BOM_Supplier Part") "C29718")
      )
      (libsource (lib "") (part "4D03WGJ0103T5E"))
    )
    (comp (ref "RN17")
      (value "10K")
      (fields
        (field (name "BOM_Manufacturer Part") "4D03WGJ0103T5E")
        (field (name "BOM_Supplier Part") "C29718")
      )
      (libsource (lib "") (part "4D03WGJ0103T5E"))
    )
    (comp (ref "RN18")
      (value "10K")
      (fields
        (field (name "BOM_Manufacturer Part") "4D03WGJ0103T5E")
        (field (name "BOM_Supplier Part") "C29718")
      )
      (libsource (lib "") (part "4D03WGJ0103T5E"))
    )
    (comp (ref "CARD1")
      (value "TF-15×15")
      (fields (field (name "BOM_Supplier Part") "C111196"))
      (libsource (lib "") (part "TF-15×15"))
    )
    (comp (ref "U6")
      (value "TXB0104PWR")
      (fields (field (name "BOM_Supplier Part") "C60708"))
      (libsource (lib "") (part "TXB0104PWR"))
    )
    (comp (ref "U8")
      (value "74HC04D,653")
      (fields (field (name "BOM_Supplier Part") "C5590"))
      (libsource (lib "") (part "74HC04D,653"))
    )
    (comp (ref "C1")
      (value "100nF")
      (fields
        (field (name "BOM_Manufacturer Part") "CC0603KRX7R9BB104")
        (field (name "BOM_Supplier Part") "C14663")
      )
      (libsource (lib "") (part "CC0603KRX7R9BB104"))
    )
    (comp (ref "C2")
      (value "100nF")
      (fields
        (field (name "BOM_Manufacturer Part") "CC0603KRX7R9BB104")
        (field (name "BOM_Supplier Part") "C14663")
      )
      (libsource (lib "") (part "CC0603KRX7R9BB104"))
    )
    (comp (ref "C3")
      (value "100nF")
      (fields
        (field (name "BOM_Manufacturer Part") "CC0603KRX7R9BB104")
        (field (name "BOM_Supplier Part") "C14663")
      )
      (libsource (lib "") (part "CC0603KRX7R9BB104"))
    )
    (comp (ref "C4")
      (value "100nF")
      (fields
        (field (name "BOM_Manufacturer Part") "CC0603KRX7R9BB104")
        (field (name "BOM_Supplier Part") "C14663")
      )
      (libsource (lib "") (part "CC0603KRX7R9BB104"))
    )
    (comp (ref "C5")
      (value "100nF")
      (fields
        (field (name "BOM_Manufacturer Part") "CC0603KRX7R9BB104")
        (field (name "BOM_Supplier Part") "C14663")
      )
      (libsource (lib "") (part "CC0603KRX7R9BB104"))
    )
    (comp (ref "C6")
      (value "100nF")
      (fields
        (field (name "BOM_Manufacturer Part") "CC0603KRX7R9BB104")
        (field (name "BOM_Supplier Part") "C14663")
      )
      (libsource (lib "") (part "CC0603KRX7R9BB104"))
    )
    (comp (ref "C7")
      (value "100nF")
      (fields
        (field (name "BOM_Manufacturer Part") "CC0603KRX7R9BB104")
        (field (name "BOM_Supplier Part") "C14663")
      )
      (libsource (lib "") (part "CC0603KRX7R9BB104"))
    )
    (comp (ref "C8")
      (value "100nF")
      (fields
        (field (name "BOM_Manufacturer Part") "CC0603KRX7R9BB104")
        (field (name "BOM_Supplier Part") "C14663")
      )
      (libsource (lib "") (part "CC0603KRX7R9BB104"))
    )
    (comp (ref "C9")
      (value "100nF")
      (fields
        (field (name "BOM_Manufacturer Part") "CC0603KRX7R9BB104")
        (field (name "BOM_Supplier Part") "C14663")
      )
      (libsource (lib "") (part "CC0603KRX7R9BB104"))
    )
    (comp (ref "C10")
      (value "100nF")
      (fields
        (field (name "BOM_Manufacturer Part") "CC0603KRX7R9BB104")
        (field (name "BOM_Supplier Part") "C14663")
      )
      (libsource (lib "") (part "CC0603KRX7R9BB104"))
    )
    (comp (ref "C11")
      (value "100nF")
      (fields
        (field (name "BOM_Manufacturer Part") "CC0603KRX7R9BB104")
        (field (name "BOM_Supplier Part") "C14663")
      )
      (libsource (lib "") (part "CC0603KRX7R9BB104"))
    )
    (comp (ref "C12")
      (value "100nF")
      (fields
        (field (name "BOM_Manufacturer Part") "CC0603KRX7R9BB104")
        (field (name "BOM_Supplier Part") "C14663")
      )
      (libsource (lib "") (part "CC0603KRX7R9BB104"))
    )
    (comp (ref "C13")
      (value "100nF")
      (fields
        (field (name "BOM_Manufacturer Part") "CC0603KRX7R9BB104")
        (field (name "BOM_Supplier Part") "C14663")
      )
      (libsource (lib "") (part "CC0603KRX7R9BB104"))
    )
    (comp (ref "C14")
      (value "100nF")
      (fields
        (field (name "BOM_Manufacturer Part") "CC0603KRX7R9BB104")
        (field (name "BOM_Supplier Part") "C14663")
      )
      (libsource (lib "") (part "CC0603KRX7R9BB104"))
    )
    (comp (ref "C15")
      (value "100nF")
      (fields
        (field (name "BOM_Manufacturer Part") "CC0603KRX7R9BB104")
        (field (name "BOM_Supplier Part") "C14663")
      )
      (libsource (lib "") (part "CC0603KRX7R9BB104"))
    )
    (comp (ref "C16")
      (value "100nF")
      (fields
        (field (name "BOM_Manufacturer Part") "CC0603KRX7R9BB104")
        (field (name "BOM_Supplier Part") "C14663")
      )
      (libsource (lib "") (part "CC0603KRX7R9BB104"))
    )
    (comp (ref "C17")
      (value "100nF")
      (fields
        (field (name "BOM_Manufacturer Part") "CC0603KRX7R9BB104")
        (field (name "BOM_Supplier Part") "C14663")
      )
      (libsource (lib "") (part "CC0603KRX7R9BB104"))
    )
    (comp (ref "C20")
      (value "100nF")
      (fields
        (field (name "BOM_Manufacturer Part") "CC0603KRX7R9BB104")
        (field (name "BOM_Supplier Part") "C14663")
      )
      (libsource (lib "") (part "CC0603KRX7R9BB104"))
    )
    (comp (ref "C21")
      (value "100nF")
      (fields
        (field (name "BOM_Manufacturer Part") "CC0603KRX7R9BB104")
        (field (name "BOM_Supplier Part") "C14663")
      )
      (libsource (lib "") (part "CC0603KRX7R9BB104"))
    )
    (comp (ref "H3")
      (value "A2541WR-4P")
      (fields (field (name "BOM_Supplier Part") "C225490"))
      (libsource (lib "") (part "A2541WR-4P"))
    )
    (comp (ref "R5")
      (value "75")
      (fields
        (field (name "BOM_Manufacturer Part") "0402WGF750JTCE")
        (field (name "BOM_Supplier Part") "C25133")
      )
      (libsource (lib "") (part "0402WGF750JTCE"))
    )
    (comp (ref "R6")
      (value "75")
      (fields
        (field (name "BOM_Manufacturer Part") "0402WGF750JTCE")
        (field (name "BOM_Supplier Part") "C25133")
      )
      (libsource (lib "") (part "0402WGF750JTCE"))
    )
    (comp (ref "U11")
      (value "PCA9517ADP,118")
      (fields (field (name "BOM_Supplier Part") "C80799"))
      (libsource (lib "") (part "PCA9517ADP,118"))
    )
    (comp (ref "ENAMEOUTINDICATOR1")
      (value "FC-2012HRK-620D")
      (fields (field (name "BOM_Supplier Part") "C84256"))
      (libsource (lib "") (part "FC-2012HRK-620D"))
    )
    (comp (ref "INPUTACTIVITYINDICATOR")
      (value "FC-2012HRK-620D")
      (fields (field (name "BOM_Supplier Part") "C84256"))
      (libsource (lib "") (part "FC-2012HRK-620D_1"))
    )
    (comp (ref "R-4-1V-INDICATOR")
      (value "220")
      (fields
        (field (name "BOM_Manufacturer Part") "0805W8F2200T5E")
        (field (name "BOM_Supplier Part") "C17557")
      )
      (libsource (lib "") (part "0805W8F2200T5E"))
    )
    (comp (ref "RESFORENAMEOUTINDICATOR1")
      (value "220")
      (fields
        (field (name "BOM_Manufacturer Part") "0805W8F2200T5E")
        (field (name "BOM_Supplier Part") "C17557")
      )
      (libsource (lib "") (part "0805W8F2200T5E_1"))
    )
    (comp (ref "U12")
      (value "ULN2003ADR")
      (fields (field (name "BOM_Supplier Part") "C7512"))
      (libsource (lib "") (part "ULN2003ADR"))
    )
  )
  (nets
    (net (code "1") (name "3.3V") (class "Default")
      (node (ref "C17") (pin "1") (pinfunction "1_1") (pintype "unspecified"))
      (node (ref "CAP1-FOR-3.3V-PS") (pin "1") (pinfunction "1_1") (pintype "input"))
      (node (ref "CARD1") (pin "4") (pinfunction "VDD_4") (pintype "input"))
      (node (ref "U1") (pin "2") (pinfunction "Vout_2") (pintype "unspecified"))
      (node (ref "U1") (pin "4") (pinfunction "Vout_4") (pintype "unspecified"))
      (node (ref "U6") (pin "1") (pinfunction "VCCA_1") (pintype "unspecified"))
      (node (ref "U6") (pin "8") (pinfunction "OE_8") (pintype "unspecified"))
    )
    (net (code "2") (name "5V") (class "Default")
      (node (ref "C1") (pin "1") (pinfunction "1_1") (pintype "unspecified"))
      (node (ref "C10") (pin "1") (pinfunction "1_1") (pintype "unspecified"))
      (node (ref "C11") (pin "1") (pinfunction "1_1") (pintype "unspecified"))
      (node (ref "C12") (pin "1") (pinfunction "1_1") (pintype "unspecified"))
      (node (ref "C13") (pin "1") (pinfunction "1_1") (pintype "unspecified"))
      (node (ref "C14") (pin "1") (pinfunction "1_1") (pintype "unspecified"))
      (node (ref "C15") (pin "1") (pinfunction "1_1") (pintype "unspecified"))
      (node (ref "C16") (pin "1") (pinfunction "1_1") (pintype "unspecified"))
      (node (ref "C18") (pin "1") (pinfunction "1_1") (pintype "input"))
      (node (ref "C2") (pin "1") (pinfunction "1_1") (pintype "unspecified"))
      (node (ref "C20") (pin "1") (pinfunction "1_1") (pintype "unspecified"))
      (node (ref "C21") (pin "1") (pinfunction "1_1") (pintype "unspecified"))
      (node (ref "C3") (pin "1") (pinfunction "1_1") (pintype "unspecified"))
      (node (ref "C4") (pin "1") (pinfunction "1_1") (pintype "unspecified"))
      (node (ref "C5") (pin "1") (pinfunction "1_1") (pintype "unspecified"))
      (node (ref "C6") (pin "1") (pinfunction "1_1") (pintype "unspecified"))
      (node (ref "C7") (pin "1") (pinfunction "1_1") (pintype "unspecified"))
      (node (ref "C8") (pin "1") (pinfunction "1_1") (pintype "unspecified"))
      (node (ref "C9") (pin "1") (pinfunction "1_1") (pintype "unspecified"))
      (node (ref "CAP2-FOR-3.3V-PS") (pin "1") (pinfunction "1_1") (pintype "input"))
      (node (ref "CN2") (pin "1") (pinfunction "1_1") (pintype "unspecified"))
      (node (ref "DECODER-01-08") (pin "16") (pinfunction "VCC_16") (pintype "unspecified"))
      (node (ref "DECODER-09-16") (pin "16") (pinfunction "VCC_16") (pintype "unspecified"))
      (node (ref "DECODER-17-24") (pin "16") (pinfunction "VCC_16") (pintype "unspecified"))
      (node (ref "DECODER-25-32") (pin "16") (pinfunction "VCC_16") (pintype "unspecified"))
      (node (ref "ENCODER-01-08") (pin "16") (pinfunction "VCC_16") (pintype "unspecified"))
      (node (ref "ENCODER-09-16") (pin "16") (pinfunction "VCC_16") (pintype "unspecified"))
      (node (ref "ENCODER-17-24") (pin "16") (pinfunction "VCC_16") (pintype "unspecified"))
      (node (ref "ENCODER-25-32") (pin "16") (pinfunction "VCC_16") (pintype "unspecified"))
      (node (ref "H3") (pin "2") (pinfunction "2_2") (pintype "unspecified"))
      (node (ref "P1") (pin "11") (pinfunction "11_11") (pintype "unspecified"))
      (node (ref "P1") (pin "12") (pinfunction "12_12") (pintype "unspecified"))
      (node (ref "P2") (pin "11") (pinfunction "11_11") (pintype "unspecified"))
      (node (ref "P2") (pin "12") (pinfunction "12_12") (pintype "unspecified"))
      (node (ref "P3") (pin "11") (pinfunction "11_11") (pintype "unspecified"))
      (node (ref "P3") (pin "12") (pinfunction "12_12") (pintype "unspecified"))
      (node (ref "P4") (pin "11") (pinfunction "11_11") (pintype "unspecified"))
      (node (ref "P4") (pin "12") (pinfunction "12_12") (pintype "unspecified"))
      (node (ref "R-4-1V-INDICATOR") (pin "1") (pinfunction "1_1") (pintype "input"))
      (node (ref "R-4-5V-INDICATOR") (pin "1") (pinfunction "1_1") (pintype "input"))
      (node (ref "RESFORENAMEOUTINDICATOR1") (pin "1") (pinfunction "1_1") (pintype "input"))
      (node (ref "RN1") (pin "5") (pinfunction "5_5") (pintype "input"))
      (node (ref "RN1") (pin "6") (pinfunction "6_6") (pintype "input"))
      (node (ref "RN1") (pin "7") (pinfunction "7_7") (pintype "input"))
      (node (ref "RN1") (pin "8") (pinfunction "8_8") (pintype "input"))
      (node (ref "RN11") (pin "5") (pinfunction "5_5") (pintype "input"))
      (node (ref "RN11") (pin "6") (pinfunction "6_6") (pintype "input"))
      (node (ref "RN11") (pin "7") (pinfunction "7_7") (pintype "input"))
      (node (ref "RN11") (pin "8") (pinfunction "8_8") (pintype "input"))
      (node (ref "RN12") (pin "5") (pinfunction "5_5") (pintype "input"))
      (node (ref "RN12") (pin "6") (pinfunction "6_6") (pintype "input"))
      (node (ref "RN12") (pin "7") (pinfunction "7_7") (pintype "input"))
      (node (ref "RN12") (pin "8") (pinfunction "8_8") (pintype "input"))
      (node (ref "RN13") (pin "5") (pinfunction "5_5") (pintype "input"))
      (node (ref "RN13") (pin "6") (pinfunction "6_6") (pintype "input"))
      (node (ref "RN13") (pin "7") (pinfunction "7_7") (pintype "input"))
      (node (ref "RN13") (pin "8") (pinfunction "8_8") (pintype "input"))
      (node (ref "RN14") (pin "5") (pinfunction "5_5") (pintype "input"))
      (node (ref "RN14") (pin "6") (pinfunction "6_6") (pintype "input"))
      (node (ref "RN14") (pin "7") (pinfunction "7_7") (pintype "input"))
      (node (ref "RN14") (pin "8") (pinfunction "8_8") (pintype "input"))
      (node (ref "RN15") (pin "5") (pinfunction "5_5") (pintype "input"))
      (node (ref "RN15") (pin "6") (pinfunction "6_6") (pintype "input"))
      (node (ref "RN15") (pin "7") (pinfunction "7_7") (pintype "input"))
      (node (ref "RN15") (pin "8") (pinfunction "8_8") (pintype "input"))
      (node (ref "RN16") (pin "5") (pinfunction "5_5") (pintype "input"))
      (node (ref "RN16") (pin "6") (pinfunction "6_6") (pintype "input"))
      (node (ref "RN16") (pin "7") (pinfunction "7_7") (pintype "input"))
      (node (ref "RN16") (pin "8") (pinfunction "8_8") (pintype "input"))
      (node (ref "RN17") (pin "5") (pinfunction "5_5") (pintype "input"))
      (node (ref "RN17") (pin "6") (pinfunction "6_6") (pintype "input"))
      (node (ref "RN17") (pin "7") (pinfunction "7_7") (pintype "input"))
      (node (ref "RN17") (pin "8") (pinfunction "8_8") (pintype "input"))
      (node (ref "RN18") (pin "5") (pinfunction "5_5") (pintype "input"))
      (node (ref "RN18") (pin "6") (pinfunction "6_6") (pintype "input"))
      (node (ref "RN18") (pin "7") (pinfunction "7_7") (pintype "input"))
      (node (ref "RN18") (pin "8") (pinfunction "8_8") (pintype "input"))
      (node (ref "RN2") (pin "5") (pinfunction "5_5") (pintype "input"))
      (node (ref "RN2") (pin "6") (pinfunction "6_6") (pintype "input"))
      (node (ref "RN2") (pin "7") (pinfunction "7_7") (pintype "input"))
      (node (ref "RN2") (pin "8") (pinfunction "8_8") (pintype "input"))
      (node (ref "U1") (pin "3") (pinfunction "Vin_3") (pintype "unspecified"))
      (node (ref "U10") (pin "1") (pinfunction "4_1") (pintype "unspecified"))
      (node (ref "U10") (pin "16") (pinfunction "VCC_16") (pintype "unspecified"))
      (node (ref "U10") (pin "2") (pinfunction "5_2") (pintype "unspecified"))
      (node (ref "U10") (pin "3") (pinfunction "6_3") (pintype "unspecified"))
      (node (ref "U10") (pin "4") (pinfunction "7_4") (pintype "unspecified"))
      (node (ref "U11") (pin "1") (pinfunction "VCCA_1") (pintype "unspecified"))
      (node (ref "U11") (pin "5") (pinfunction "EN_5") (pintype "unspecified"))
      (node (ref "U11") (pin "8") (pinfunction "VCCB_8") (pintype "unspecified"))
      (node (ref "U2") (pin "14") (pinfunction "VDD_14") (pintype "unspecified"))
      (node (ref "U3") (pin "18") (pinfunction "AVCC_18") (pintype "unspecified"))
      (node (ref "U3") (pin "4") (pinfunction "VCC_4") (pintype "unspecified"))
      (node (ref "U3") (pin "6") (pinfunction "VCC_6") (pintype "unspecified"))
      (node (ref "U4") (pin "14") (pinfunction "VDD_14") (pintype "unspecified"))
      (node (ref "U5") (pin "4") (pinfunction "+Vo_4") (pintype "unspecified"))
      (node (ref "U6") (pin "14") (pinfunction "VCCB_14") (pintype "unspecified"))
      (node (ref "U7") (pin "16") (pinfunction "VCC_16") (pintype "unspecified"))
      (node (ref "U8") (pin "14") (pinfunction "VCC_14") (pintype "unspecified"))
      (node (ref "USB2") (pin "1") (pinfunction "VBUS_1") (pintype "unspecified"))
    )
    (net (code "3") (name "12V") (class "Default")
      (node (ref "C19") (pin "1") (pinfunction "1_1") (pintype "input"))
      (node (ref "H4") (pin "3") (pinfunction "3_3") (pintype "unspecified"))
      (node (ref "R-4-12V-INDICATOR") (pin "1") (pinfunction "1_1") (pintype "input"))
      (node (ref "U9") (pin "4") (pinfunction "+VO_4") (pintype "unspecified"))
    )
    (net (code "4") (name "AND-01-A0") (class "Default")
      (node (ref "ENCODER-01-08") (pin "9") (pinfunction "A0_9") (pintype "unspecified"))
      (node (ref "U4") (pin "2") (pinfunction "D_2") (pintype "unspecified"))
    )
    (net (code "5") (name "AND-01-A1") (class "Default")
      (node (ref "ENCODER-01-08") (pin "7") (pinfunction "A1_7") (pintype "unspecified"))
      (node (ref "U4") (pin "12") (pinfunction "H_12") (pintype "unspecified"))
    )
    (net (code "6") (name "AND-01-A2") (class "Default")
      (node (ref "ENCODER-01-08") (pin "6") (pinfunction "A2_6") (pintype "unspecified"))
      (node (ref "U2") (pin "2") (pinfunction "D_2") (pintype "unspecified"))
    )
    (net (code "7") (name "AND-02-A0") (class "Default")
      (node (ref "ENCODER-09-16") (pin "9") (pinfunction "A0_9") (pintype "unspecified"))
      (node (ref "U4") (pin "3") (pinfunction "C_3") (pintype "unspecified"))
    )
    (net (code "8") (name "AND-02-A1") (class "Default")
      (node (ref "ENCODER-09-16") (pin "7") (pinfunction "A1_7") (pintype "unspecified"))
      (node (ref "U4") (pin "11") (pinfunction "G_11") (pintype "unspecified"))
    )
    (net (code "9") (name "AND-02-A2") (class "Default")
      (node (ref "ENCODER-09-16") (pin "6") (pinfunction "A2_6") (pintype "unspecified"))
      (node (ref "U2") (pin "3") (pinfunction "C_3") (pintype "unspecified"))
    )
    (net (code "10") (name "AND-03-A0") (class "Default")
      (node (ref "ENCODER-17-24") (pin "9") (pinfunction "A0_9") (pintype "unspecified"))
      (node (ref "U4") (pin "4") (pinfunction "B_4") (pintype "unspecified"))
    )
    (net (code "11") (name "AND-03-A1") (class "Default")
      (node (ref "ENCODER-17-24") (pin "7") (pinfunction "A1_7") (pintype "unspecified"))
      (node (ref "U4") (pin "10") (pinfunction "F_10") (pintype "unspecified"))
    )
    (net (code "12") (name "AND-03-A2") (class "Default")
      (node (ref "ENCODER-17-24") (pin "6") (pinfunction "A2_6") (pintype "unspecified"))
      (node (ref "U2") (pin "4") (pinfunction "B_4") (pintype "unspecified"))
    )
    (net (code "13") (name "AND-04-A0") (class "Default")
      (node (ref "ENCODER-25-32") (pin "9") (pinfunction "A0_9") (pintype "unspecified"))
      (node (ref "U4") (pin "5") (pinfunction "A_5") (pintype "unspecified"))
    )
    (net (code "14") (name "AND-04-A1") (class "Default")
      (node (ref "ENCODER-25-32") (pin "7") (pinfunction "A1_7") (pintype "unspecified"))
      (node (ref "U4") (pin "9") (pinfunction "E_9") (pintype "unspecified"))
    )
    (net (code "15") (name "AND-04-A2") (class "Default")
      (node (ref "ENCODER-25-32") (pin "6") (pinfunction "A2_6") (pintype "unspecified"))
      (node (ref "U2") (pin "5") (pinfunction "A_5") (pintype "unspecified"))
    )
    (net (code "16") (name "AREF") (class "Default")
      (node (ref "CAP-4-ANALOG-REF") (pin "1") (pinfunction "1_1") (pintype "unspecified"))
      (node (ref "U3") (pin "20") (pinfunction "AREF_20") (pintype "unspecified"))
    )
    (net (code "17") (name "BTN-01") (class "Default")
      (node (ref "ENCODER-01-08") (pin "10") (pinfunction "0_10") (pintype "unspecified"))
      (node (ref "H7") (pin "1") (pinfunction "1_1") (pintype "unspecified"))
      (node (ref "RN11") (pin "4") (pinfunction "4_4") (pintype "input"))
    )
    (net (code "18") (name "BTN-02") (class "Default")
      (node (ref "ENCODER-01-08") (pin "11") (pinfunction "1_11") (pintype "unspecified"))
      (node (ref "H7") (pin "2") (pinfunction "2_2") (pintype "unspecified"))
      (node (ref "RN11") (pin "3") (pinfunction "3_3") (pintype "input"))
    )
    (net (code "19") (name "BTN-03") (class "Default")
      (node (ref "ENCODER-01-08") (pin "12") (pinfunction "2_12") (pintype "unspecified"))
      (node (ref "H7") (pin "3") (pinfunction "3_3") (pintype "unspecified"))
      (node (ref "RN11") (pin "2") (pinfunction "2_2") (pintype "input"))
    )
    (net (code "20") (name "BTN-04") (class "Default")
      (node (ref "ENCODER-01-08") (pin "13") (pinfunction "3_13") (pintype "unspecified"))
      (node (ref "H7") (pin "4") (pinfunction "4_4") (pintype "unspecified"))
      (node (ref "RN11") (pin "1") (pinfunction "1_1") (pintype "input"))
    )
    (net (code "21") (name "BTN-05") (class "Default")
      (node (ref "ENCODER-01-08") (pin "1") (pinfunction "4_1") (pintype "unspecified"))
      (node (ref "H7") (pin "5") (pinfunction "5_5") (pintype "unspecified"))
      (node (ref "RN12") (pin "4") (pinfunction "4_4") (pintype "input"))
    )
    (net (code "22") (name "BTN-06") (class "Default")
      (node (ref "ENCODER-01-08") (pin "2") (pinfunction "5_2") (pintype "unspecified"))
      (node (ref "H7") (pin "6") (pinfunction "6_6") (pintype "unspecified"))
      (node (ref "RN12") (pin "3") (pinfunction "3_3") (pintype "input"))
    )
    (net (code "23") (name "BTN-07") (class "Default")
      (node (ref "ENCODER-01-08") (pin "3") (pinfunction "6_3") (pintype "unspecified"))
      (node (ref "H7") (pin "7") (pinfunction "7_7") (pintype "unspecified"))
      (node (ref "RN12") (pin "2") (pinfunction "2_2") (pintype "input"))
    )
    (net (code "24") (name "BTN-08") (class "Default")
      (node (ref "ENCODER-01-08") (pin "4") (pinfunction "7_4") (pintype "unspecified"))
      (node (ref "H7") (pin "8") (pinfunction "8_8") (pintype "unspecified"))
      (node (ref "RN12") (pin "1") (pinfunction "1_1") (pintype "input"))
    )
    (net (code "25") (name "BTN-09") (class "Default")
      (node (ref "ENCODER-09-16") (pin "10") (pinfunction "0_10") (pintype "unspecified"))
      (node (ref "H8") (pin "1") (pinfunction "1_1") (pintype "unspecified"))
      (node (ref "RN13") (pin "4") (pinfunction "4_4") (pintype "input"))
    )
    (net (code "26") (name "BTN-10") (class "Default")
      (node (ref "ENCODER-09-16") (pin "11") (pinfunction "1_11") (pintype "unspecified"))
      (node (ref "H8") (pin "2") (pinfunction "2_2") (pintype "unspecified"))
      (node (ref "RN13") (pin "3") (pinfunction "3_3") (pintype "input"))
    )
    (net (code "27") (name "BTN-11") (class "Default")
      (node (ref "ENCODER-09-16") (pin "12") (pinfunction "2_12") (pintype "unspecified"))
      (node (ref "H8") (pin "3") (pinfunction "3_3") (pintype "unspecified"))
      (node (ref "RN13") (pin "2") (pinfunction "2_2") (pintype "input"))
    )
    (net (code "28") (name "BTN-12") (class "Default")
      (node (ref "ENCODER-09-16") (pin "13") (pinfunction "3_13") (pintype "unspecified"))
      (node (ref "H8") (pin "4") (pinfunction "4_4") (pintype "unspecified"))
      (node (ref "RN13") (pin "1") (pinfunction "1_1") (pintype "input"))
    )
    (net (code "29") (name "BTN-13") (class "Default")
      (node (ref "ENCODER-09-16") (pin "1") (pinfunction "4_1") (pintype "unspecified"))
      (node (ref "H8") (pin "5") (pinfunction "5_5") (pintype "unspecified"))
      (node (ref "RN14") (pin "4") (pinfunction "4_4") (pintype "input"))
    )
    (net (code "30") (name "BTN-14") (class "Default")
      (node (ref "ENCODER-09-16") (pin "2") (pinfunction "5_2") (pintype "unspecified"))
      (node (ref "H8") (pin "6") (pinfunction "6_6") (pintype "unspecified"))
      (node (ref "RN14") (pin "3") (pinfunction "3_3") (pintype "input"))
    )
    (net (code "31") (name "BTN-15") (class "Default")
      (node (ref "ENCODER-09-16") (pin "3") (pinfunction "6_3") (pintype "unspecified"))
      (node (ref "H8") (pin "7") (pinfunction "7_7") (pintype "unspecified"))
      (node (ref "RN14") (pin "2") (pinfunction "2_2") (pintype "input"))
    )
    (net (code "32") (name "BTN-16") (class "Default")
      (node (ref "ENCODER-09-16") (pin "4") (pinfunction "7_4") (pintype "unspecified"))
      (node (ref "H8") (pin "8") (pinfunction "8_8") (pintype "unspecified"))
      (node (ref "RN14") (pin "1") (pinfunction "1_1") (pintype "input"))
    )
    (net (code "33") (name "BTN-17") (class "Default")
      (node (ref "ENCODER-17-24") (pin "10") (pinfunction "0_10") (pintype "unspecified"))
      (node (ref "H9") (pin "1") (pinfunction "1_1") (pintype "unspecified"))
      (node (ref "RN15") (pin "4") (pinfunction "4_4") (pintype "input"))
    )
    (net (code "34") (name "BTN-18") (class "Default")
      (node (ref "ENCODER-17-24") (pin "11") (pinfunction "1_11") (pintype "unspecified"))
      (node (ref "H9") (pin "2") (pinfunction "2_2") (pintype "unspecified"))
      (node (ref "RN15") (pin "3") (pinfunction "3_3") (pintype "input"))
    )
    (net (code "35") (name "BTN-19") (class "Default")
      (node (ref "ENCODER-17-24") (pin "12") (pinfunction "2_12") (pintype "unspecified"))
      (node (ref "H9") (pin "3") (pinfunction "3_3") (pintype "unspecified"))
      (node (ref "RN15") (pin "2") (pinfunction "2_2") (pintype "input"))
    )
    (net (code "36") (name "BTN-20") (class "Default")
      (node (ref "ENCODER-17-24") (pin "13") (pinfunction "3_13") (pintype "unspecified"))
      (node (ref "H9") (pin "4") (pinfunction "4_4") (pintype "unspecified"))
      (node (ref "RN15") (pin "1") (pinfunction "1_1") (pintype "input"))
    )
    (net (code "37") (name "BTN-21") (class "Default")
      (node (ref "ENCODER-17-24") (pin "1") (pinfunction "4_1") (pintype "unspecified"))
      (node (ref "H9") (pin "5") (pinfunction "5_5") (pintype "unspecified"))
      (node (ref "RN16") (pin "4") (pinfunction "4_4") (pintype "input"))
    )
    (net (code "38") (name "BTN-22") (class "Default")
      (node (ref "ENCODER-17-24") (pin "2") (pinfunction "5_2") (pintype "unspecified"))
      (node (ref "H9") (pin "6") (pinfunction "6_6") (pintype "unspecified"))
      (node (ref "RN16") (pin "3") (pinfunction "3_3") (pintype "input"))
    )
    (net (code "39") (name "BTN-23") (class "Default")
      (node (ref "ENCODER-17-24") (pin "3") (pinfunction "6_3") (pintype "unspecified"))
      (node (ref "H9") (pin "7") (pinfunction "7_7") (pintype "unspecified"))
      (node (ref "RN16") (pin "2") (pinfunction "2_2") (pintype "input"))
    )
    (net (code "40") (name "BTN-24") (class "Default")
      (node (ref "ENCODER-17-24") (pin "4") (pinfunction "7_4") (pintype "unspecified"))
      (node (ref "H9") (pin "8") (pinfunction "8_8") (pintype "unspecified"))
      (node (ref "RN16") (pin "1") (pinfunction "1_1") (pintype "input"))
    )
    (net (code "41") (name "BTN-25") (class "Default")
      (node (ref "ENCODER-25-32") (pin "10") (pinfunction "0_10") (pintype "unspecified"))
      (node (ref "H10") (pin "1") (pinfunction "1_1") (pintype "unspecified"))
      (node (ref "RN17") (pin "4") (pinfunction "4_4") (pintype "input"))
    )
    (net (code "42") (name "BTN-26") (class "Default")
      (node (ref "ENCODER-25-32") (pin "11") (pinfunction "1_11") (pintype "unspecified"))
      (node (ref "H10") (pin "2") (pinfunction "2_2") (pintype "unspecified"))
      (node (ref "RN17") (pin "3") (pinfunction "3_3") (pintype "input"))
    )
    (net (code "43") (name "BTN-27") (class "Default")
      (node (ref "ENCODER-25-32") (pin "12") (pinfunction "2_12") (pintype "unspecified"))
      (node (ref "H10") (pin "3") (pinfunction "3_3") (pintype "unspecified"))
      (node (ref "RN17") (pin "2") (pinfunction "2_2") (pintype "input"))
    )
    (net (code "44") (name "BTN-28") (class "Default")
      (node (ref "ENCODER-25-32") (pin "13") (pinfunction "3_13") (pintype "unspecified"))
      (node (ref "H10") (pin "4") (pinfunction "4_4") (pintype "unspecified"))
      (node (ref "RN17") (pin "1") (pinfunction "1_1") (pintype "input"))
    )
    (net (code "45") (name "BTN-29") (class "Default")
      (node (ref "ENCODER-25-32") (pin "1") (pinfunction "4_1") (pintype "unspecified"))
      (node (ref "H10") (pin "5") (pinfunction "5_5") (pintype "unspecified"))
      (node (ref "RN18") (pin "4") (pinfunction "4_4") (pintype "input"))
    )
    (net (code "46") (name "BTN-30") (class "Default")
      (node (ref "ENCODER-25-32") (pin "2") (pinfunction "5_2") (pintype "unspecified"))
      (node (ref "H10") (pin "6") (pinfunction "6_6") (pintype "unspecified"))
      (node (ref "RN18") (pin "3") (pinfunction "3_3") (pintype "input"))
    )
    (net (code "47") (name "BTN-31") (class "Default")
      (node (ref "ENCODER-25-32") (pin "3") (pinfunction "6_3") (pintype "unspecified"))
      (node (ref "H10") (pin "7") (pinfunction "7_7") (pintype "unspecified"))
      (node (ref "RN18") (pin "2") (pinfunction "2_2") (pintype "input"))
    )
    (net (code "48") (name "BTN-32") (class "Default")
      (node (ref "ENCODER-25-32") (pin "4") (pinfunction "7_4") (pintype "unspecified"))
      (node (ref "H10") (pin "8") (pinfunction "8_8") (pintype "unspecified"))
      (node (ref "RN18") (pin "1") (pinfunction "1_1") (pintype "input"))
    )
    (net (code "49") (name "COIN") (class "Default")
      (node (ref "H4") (pin "2") (pinfunction "2_2") (pintype "unspecified"))
      (node (ref "RN2") (pin "1") (pinfunction "1_1") (pintype "input"))
      (node (ref "U3") (pin "32") (pinfunction "PD2(INT0/PCINT18)_32") (pintype "unspecified"))
    )
    (net (code "50") (name "CONFIG") (class "Default")
      (node (ref "PROG-BUTTON") (pin "1") (pinfunction "1_1") (pintype "unspecified"))
      (node (ref "PROG-BUTTON") (pin "2") (pinfunction "2_2") (pintype "unspecified"))
      (node (ref "RN2") (pin "2") (pinfunction "2_2") (pintype "input"))
      (node (ref "U3") (pin "1") (pinfunction "(PCINT19/OC2B/INT1)PD3_1") (pintype "unspecified"))
    )
    (net (code "51") (name "DEC-EN-00") (class "Default")
      (node (ref "DECODER-01-08") (pin "4") (pinfunction "E1#_4") (pintype "unspecified"))
      (node (ref "U7") (pin "15") (pinfunction "Y0#_15") (pintype "unspecified"))
    )
    (net (code "52") (name "DEC-EN-01") (class "Default")
      (node (ref "DECODER-09-16") (pin "4") (pinfunction "E1#_4") (pintype "unspecified"))
      (node (ref "U7") (pin "14") (pinfunction "Y1#_14") (pintype "unspecified"))
    )
    (net (code "53") (name "DEC-EN-02") (class "Default")
      (node (ref "DECODER-17-24") (pin "4") (pinfunction "E1#_4") (pintype "unspecified"))
      (node (ref "U7") (pin "13") (pinfunction "Y2#_13") (pintype "unspecified"))
    )
    (net (code "54") (name "DEC-EN-03") (class "Default")
      (node (ref "DECODER-25-32") (pin "4") (pinfunction "E1#_4") (pintype "unspecified"))
      (node (ref "U7") (pin "12") (pinfunction "Y3#_12") (pintype "unspecified"))
    )
    (net (code "55") (name "DISP-SCL") (class "Default")
      (node (ref "H3") (pin "4") (pinfunction "4_4") (pintype "unspecified"))
      (node (ref "R5") (pin "1") (pinfunction "1_1") (pintype "input"))
      (node (ref "RN1") (pin "4") (pinfunction "4_4") (pintype "input"))
    )
    (net (code "56") (name "DISP-SDA") (class "Default")
      (node (ref "H3") (pin "3") (pinfunction "3_3") (pintype "unspecified"))
      (node (ref "R6") (pin "1") (pinfunction "1_1") (pintype "input"))
      (node (ref "RN1") (pin "3") (pinfunction "3_3") (pintype "input"))
    )
    (net (code "57") (name "ENABLE-OUT") (class "Default")
      (node (ref "DECODER-01-08") (pin "6") (pinfunction "E3_6") (pintype "unspecified"))
      (node (ref "DECODER-09-16") (pin "6") (pinfunction "E3_6") (pintype "unspecified"))
      (node (ref "DECODER-17-24") (pin "6") (pinfunction "E3_6") (pintype "unspecified"))
      (node (ref "DECODER-25-32") (pin "6") (pinfunction "E3_6") (pintype "unspecified"))
      (node (ref "U12") (pin "5") (pinfunction "5B_5") (pintype "unspecified"))
      (node (ref "U3") (pin "9") (pinfunction "(PCINT21/OC0B/T1)PD5_9") (pintype "unspecified"))
      (node (ref "U7") (pin "6") (pinfunction "E3_6") (pintype "unspecified"))
    )
    (net (code "58") (name "ENC-BRG-2-1") (class "Default")
      (node (ref "ENCODER-01-08") (pin "5") (pinfunction "EI_5") (pintype "unspecified"))
      (node (ref "ENCODER-09-16") (pin "15") (pinfunction "EO_15") (pintype "unspecified"))
    )
    (net (code "59") (name "ENC-BRG-3-2") (class "Default")
      (node (ref "ENCODER-09-16") (pin "5") (pinfunction "EI_5") (pintype "unspecified"))
      (node (ref "ENCODER-17-24") (pin "15") (pinfunction "EO_15") (pintype "unspecified"))
    )
    (net (code "60") (name "ENC-BRG-4-3") (class "Default")
      (node (ref "ENCODER-17-24") (pin "5") (pinfunction "EI_5") (pintype "unspecified"))
      (node (ref "ENCODER-25-32") (pin "15") (pinfunction "EO_15") (pintype "unspecified"))
    )
    (net (code "61") (name "ENC-GS-01") (class "Default")
      (node (ref "ENCODER-01-08") (pin "14") (pinfunction "GS_14") (pintype "unspecified"))
      (node (ref "U10") (pin "10") (pinfunction "0_10") (pintype "unspecified"))
    )
    (net (code "62") (name "ENC-GS-02") (class "Default")
      (node (ref "ENCODER-09-16") (pin "14") (pinfunction "GS_14") (pintype "unspecified"))
      (node (ref "U10") (pin "11") (pinfunction "1_11") (pintype "unspecified"))
    )
    (net (code "63") (name "ENC-GS-03") (class "Default")
      (node (ref "ENCODER-17-24") (pin "14") (pinfunction "GS_14") (pintype "unspecified"))
      (node (ref "U10") (pin "12") (pinfunction "2_12") (pintype "unspecified"))
    )
    (net (code "64") (name "ENC-GS-04") (class "Default")
      (node (ref "ENCODER-25-32") (pin "14") (pinfunction "GS_14") (pintype "unspecified"))
      (node (ref "U10") (pin "13") (pinfunction "3_13") (pintype "unspecified"))
    )
    (net (code "65") (name "GND") (class "Default")
      (node (ref "12V-INDICATOR") (pin "1") (pinfunction "-_1") (pintype "unspecified"))
      (node (ref "5V-INDICATOR") (pin "1") (pinfunction "-_1") (pintype "unspecified"))
      (node (ref "C1") (pin "2") (pinfunction "2_2") (pintype "unspecified"))
      (node (ref "C10") (pin "2") (pinfunction "2_2") (pintype "unspecified"))
      (node (ref "C11") (pin "2") (pinfunction "2_2") (pintype "unspecified"))
      (node (ref "C12") (pin "2") (pinfunction "2_2") (pintype "unspecified"))
      (node (ref "C13") (pin "2") (pinfunction "2_2") (pintype "unspecified"))
      (node (ref "C14") (pin "2") (pinfunction "2_2") (pintype "unspecified"))
      (node (ref "C15") (pin "2") (pinfunction "2_2") (pintype "unspecified"))
      (node (ref "C16") (pin "2") (pinfunction "2_2") (pintype "unspecified"))
      (node (ref "C17") (pin "2") (pinfunction "2_2") (pintype "unspecified"))
      (node (ref "C18") (pin "2") (pinfunction "2_2") (pintype "input"))
      (node (ref "C19") (pin "2") (pinfunction "2_2") (pintype "input"))
      (node (ref "C2") (pin "2") (pinfunction "2_2") (pintype "unspecified"))
      (node (ref "C20") (pin "2") (pinfunction "2_2") (pintype "unspecified"))
      (node (ref "C21") (pin "2") (pinfunction "2_2") (pintype "unspecified"))
      (node (ref "C3") (pin "2") (pinfunction "2_2") (pintype "unspecified"))
      (node (ref "C4") (pin "2") (pinfunction "2_2") (pintype "unspecified"))
      (node (ref "C5") (pin "2") (pinfunction "2_2") (pintype "unspecified"))
      (node (ref "C6") (pin "2") (pinfunction "2_2") (pintype "unspecified"))
      (node (ref "C7") (pin "2") (pinfunction "2_2") (pintype "unspecified"))
      (node (ref "C8") (pin "2") (pinfunction "2_2") (pintype "unspecified"))
      (node (ref "C9") (pin "2") (pinfunction "2_2") (pintype "unspecified"))
      (node (ref "CAP-4-ANALOG-REF") (pin "2") (pinfunction "2_2") (pintype "unspecified"))
      (node (ref "CAP1-FOR-3.3V-PS") (pin "2") (pinfunction "2_2") (pintype "input"))
      (node (ref "CAP2-FOR-3.3V-PS") (pin "2") (pinfunction "2_2") (pintype "input"))
      (node (ref "CARD1") (pin "10") (pinfunction "G3_10") (pintype "input"))
      (node (ref "CARD1") (pin "11") (pinfunction "G4_11") (pintype "input"))
      (node (ref "CARD1") (pin "12") (pinfunction "G1_12") (pintype "input"))
      (node (ref "CARD1") (pin "13") (pinfunction "G2_13") (pintype "input"))
      (node (ref "CARD1") (pin "6") (pinfunction "VSS_6") (pintype "input"))
      (node (ref "CN2") (pin "2") (pinfunction "2_2") (pintype "unspecified"))
      (node (ref "CRYSTAL-CAP-1") (pin "1") (pinfunction "1_1") (pintype "input"))
      (node (ref "CRYSTAL-CAP-2") (pin "1") (pinfunction "1_1") (pintype "input"))
      (node (ref "DECODER-01-08") (pin "5") (pinfunction "E2#_5") (pintype "unspecified"))
      (node (ref "DECODER-01-08") (pin "8") (pinfunction "GND_8") (pintype "unspecified"))
      (node (ref "DECODER-09-16") (pin "5") (pinfunction "E2#_5") (pintype "unspecified"))
      (node (ref "DECODER-09-16") (pin "8") (pinfunction "GND_8") (pintype "unspecified"))
      (node (ref "DECODER-17-24") (pin "5") (pinfunction "E2#_5") (pintype "unspecified"))
      (node (ref "DECODER-17-24") (pin "8") (pinfunction "GND_8") (pintype "unspecified"))
      (node (ref "DECODER-25-32") (pin "5") (pinfunction "E2#_5") (pintype "unspecified"))
      (node (ref "DECODER-25-32") (pin "8") (pinfunction "GND_8") (pintype "unspecified"))
      (node (ref "ENCODER-01-08") (pin "8") (pinfunction "GND_8") (pintype "unspecified"))
      (node (ref "ENCODER-09-16") (pin "8") (pinfunction "GND_8") (pintype "unspecified"))
      (node (ref "ENCODER-17-24") (pin "8") (pinfunction "GND_8") (pintype "unspecified"))
      (node (ref "ENCODER-25-32") (pin "5") (pinfunction "EI_5") (pintype "unspecified"))
      (node (ref "ENCODER-25-32") (pin "8") (pinfunction "GND_8") (pintype "unspecified"))
      (node (ref "H3") (pin "1") (pinfunction "1_1") (pintype "unspecified"))
      (node (ref "H4") (pin "1") (pinfunction "1_1") (pintype "unspecified"))
      (node (ref "P1") (pin "1") (pinfunction "1_1") (pintype "unspecified"))
      (node (ref "P1") (pin "2") (pinfunction "2_2") (pintype "unspecified"))
      (node (ref "P2") (pin "1") (pinfunction "1_1") (pintype "unspecified"))
      (node (ref "P2") (pin "2") (pinfunction "2_2") (pintype "unspecified"))
      (node (ref "P3") (pin "1") (pinfunction "1_1") (pintype "unspecified"))
      (node (ref "P3") (pin "2") (pinfunction "2_2") (pintype "unspecified"))
      (node (ref "P4") (pin "1") (pinfunction "1_1") (pintype "unspecified"))
      (node (ref "P4") (pin "2") (pinfunction "2_2") (pintype "unspecified"))
      (node (ref "PROG-BUTTON") (pin "3") (pinfunction "3_3") (pintype "unspecified"))
      (node (ref "PROG-BUTTON") (pin "4") (pinfunction "4_4") (pintype "unspecified"))
      (node (ref "U1") (pin "1") (pinfunction "GND/ADJ_1") (pintype "unspecified"))
      (node (ref "U10") (pin "5") (pinfunction "EI_5") (pintype "unspecified"))
      (node (ref "U10") (pin "8") (pinfunction "GND_8") (pintype "unspecified"))
      (node (ref "U11") (pin "4") (pinfunction "GND_4") (pintype "unspecified"))
      (node (ref "U12") (pin "8") (pinfunction "E_8") (pintype "unspecified"))
      (node (ref "U2") (pin "7") (pinfunction "VSS_7") (pintype "unspecified"))
      (node (ref "U3") (pin "21") (pinfunction "GND_21") (pintype "unspecified"))
      (node (ref "U3") (pin "3") (pinfunction "GND_3") (pintype "unspecified"))
      (node (ref "U3") (pin "5") (pinfunction "GND_5") (pintype "unspecified"))
      (node (ref "U4") (pin "7") (pinfunction "VSS_7") (pintype "unspecified"))
      (node (ref "U5") (pin "3") (pinfunction "-Vo_3") (pintype "unspecified"))
      (node (ref "U6") (pin "7") (pinfunction "GND_7") (pintype "unspecified"))
      (node (ref "U7") (pin "3") (pinfunction "A2_3") (pintype "unspecified"))
      (node (ref "U7") (pin "4") (pinfunction "E1#_4") (pintype "unspecified"))
      (node (ref "U7") (pin "5") (pinfunction "E2#_5") (pintype "unspecified"))
      (node (ref "U7") (pin "8") (pinfunction "GND_8") (pintype "unspecified"))
      (node (ref "U8") (pin "7") (pinfunction "GND_7") (pintype "unspecified"))
      (node (ref "U9") (pin "3") (pinfunction "-VO_3") (pintype "unspecified"))
      (node (ref "USB2") (pin "6") (pinfunction "6_6") (pintype "unspecified"))
      (node (ref "X2") (pin "2") (pinfunction "GND_2") (pintype "unspecified"))
      (node (ref "X2") (pin "4") (pinfunction "GND_4") (pintype "unspecified"))
    )
    (net (code "66") (name "ICSP-MISO") (class "Default")
      (node (ref "U3") (pin "16") (pinfunction "(PCINT4/MISO)PB4_16") (pintype "unspecified"))
      (node (ref "U6") (pin "13") (pinfunction "B1_13") (pintype "unspecified"))
      (node (ref "USB2") (pin "2") (pinfunction "D-_2") (pintype "unspecified"))
    )
    (net (code "67") (name "ICSP-MOSI") (class "Default")
      (node (ref "RN2") (pin "3") (pinfunction "3_3") (pintype "input"))
      (node (ref "U3") (pin "15") (pinfunction "(PCINT3/OC2A/MOSI)PB3_15") (pintype "unspecified"))
      (node (ref "U6") (pin "11") (pinfunction "B3_11") (pintype "unspecified"))
      (node (ref "USB2") (pin "4") (pinfunction "ID_4") (pintype "unspecified"))
    )
    (net (code "68") (name "ICSP-RESET") (class "Default")
      (node (ref "RN2") (pin "4") (pinfunction "4_4") (pintype "input"))
      (node (ref "U3") (pin "29") (pinfunction "PC6(RESET#/PCINT14)_29") (pintype "unspecified"))
      (node (ref "U8") (pin "1") (pinfunction "1A_1") (pintype "unspecified"))
      (node (ref "USB2") (pin "5") (pinfunction "GND_5") (pintype "unspecified"))
    )
    (net (code "69") (name "ICSP-SCK") (class "Default")
      (node (ref "U3") (pin "17") (pinfunction "PB5(SCK/PCINT5)_17") (pintype "unspecified"))
      (node (ref "U6") (pin "12") (pinfunction "B2_12") (pintype "unspecified"))
      (node (ref "USB2") (pin "3") (pinfunction "D+_3") (pintype "unspecified"))
    )
    (net (code "70") (name "INP-00") (class "Default")
      (node (ref "U3") (pin "25") (pinfunction "PC2(ADC2/PCINT10)_25") (pintype "unspecified"))
      (node (ref "U4") (pin "1") (pinfunction "J=A*B*C*D_1") (pintype "unspecified"))
    )
    (net (code "71") (name "INP-01") (class "Default")
      (node (ref "U3") (pin "26") (pinfunction "PC3(ADC3/PCINT11)_26") (pintype "unspecified"))
      (node (ref "U4") (pin "13") (pinfunction "K=E*F*G*H_13") (pintype "unspecified"))
    )
    (net (code "72") (name "INP-02") (class "Default")
      (node (ref "U2") (pin "1") (pinfunction "J=A*B*C*D_1") (pintype "unspecified"))
      (node (ref "U3") (pin "2") (pinfunction "(PCINT20/XCK/T0)PD4_2") (pintype "unspecified"))
      (node (ref "U3") (pin "23") (pinfunction "PC0(ADC0/PCINT8)_23") (pintype "unspecified"))
    )
    (net (code "73") (name "INP-03") (class "Default")
      (node (ref "U10") (pin "9") (pinfunction "A0_9") (pintype "unspecified"))
      (node (ref "U3") (pin "24") (pinfunction "PC1(ADC1/PCINT9)_24") (pintype "unspecified"))
    )
    (net (code "74") (name "INP-04") (class "Default")
      (node (ref "U10") (pin "7") (pinfunction "A1_7") (pintype "unspecified"))
      (node (ref "U3") (pin "30") (pinfunction "PD0(RXD/PCINT16)_30") (pintype "unspecified"))
    )
    (net (code "75") (name "INP-ACTIVITY") (class "Default")
      (node (ref "U10") (pin "14") (pinfunction "GS_14") (pintype "unspecified"))
      (node (ref "U12") (pin "1") (pinfunction "1B_1") (pintype "unspecified"))
      (node (ref "U3") (pin "31") (pinfunction "PD1(TXD/PCINT17)_31") (pintype "unspecified"))
    )
    (net (code "76") (name "LINE") (class "Default")
      (node (ref "CN1") (pin "1") (pinfunction "1_1") (pintype "unspecified"))
      (node (ref "U5") (pin "2") (pinfunction "AC_2") (pintype "unspecified"))
      (node (ref "U9") (pin "1") (pinfunction "AC_1") (pintype "unspecified"))
    )
    (net (code "77") (name "NEUTRAL") (class "Default")
      (node (ref "CN1") (pin "2") (pinfunction "2_2") (pintype "unspecified"))
      (node (ref "U5") (pin "1") (pinfunction "AC_1") (pintype "unspecified"))
      (node (ref "U9") (pin "2") (pinfunction "AC_2") (pintype "unspecified"))
    )
    (net (code "78") (name "Net-(5V-INDICATOR-+)") (class "Default")
      (node (ref "5V-INDICATOR") (pin "2") (pinfunction "+_2") (pintype "unspecified"))
      (node (ref "R-4-5V-INDICATOR") (pin "2") (pinfunction "2_2") (pintype "input"))
    )
    (net (code "79") (name "Net-(12V-INDICATOR-+)") (class "Default")
      (node (ref "12V-INDICATOR") (pin "2") (pinfunction "+_2") (pintype "unspecified"))
      (node (ref "R-4-12V-INDICATOR") (pin "2") (pinfunction "2_2") (pintype "input"))
    )
    (net (code "80") (name "Net-(ENAMEOUTINDICATOR1-+)") (class "Default")
      (node (ref "ENAMEOUTINDICATOR1") (pin "2") (pinfunction "+_2") (pintype "unspecified"))
      (node (ref "RESFORENAMEOUTINDICATOR1") (pin "2") (pinfunction "2_2") (pintype "input"))
    )
    (net (code "81") (name "Net-(ENAMEOUTINDICATOR1--)") (class "Default")
      (node (ref "ENAMEOUTINDICATOR1") (pin "1") (pinfunction "-_1") (pintype "unspecified"))
      (node (ref "U12") (pin "12") (pinfunction "5C_12") (pintype "unspecified"))
    )
    (net (code "82") (name "Net-(INPUTACTIVITYINDICATOR-+)") (class "Default")
      (node (ref "INPUTACTIVITYINDICATOR") (pin "2") (pinfunction "+_2") (pintype "unspecified"))
      (node (ref "R-4-1V-INDICATOR") (pin "2") (pinfunction "2_2") (pintype "input"))
    )
    (net (code "83") (name "Net-(INPUTACTIVITYINDICATOR--)") (class "Default")
      (node (ref "INPUTACTIVITYINDICATOR") (pin "1") (pinfunction "-_1") (pintype "unspecified"))
      (node (ref "U12") (pin "16") (pinfunction "1C_16") (pintype "unspecified"))
    )
    (net (code "84") (name "Net-(U11-SCLA)") (class "Default")
      (node (ref "R5") (pin "2") (pinfunction "2_2") (pintype "input"))
      (node (ref "U11") (pin "2") (pinfunction "SCLA_2") (pintype "unspecified"))
    )
    (net (code "85") (name "Net-(U11-SDAA)") (class "Default")
      (node (ref "R6") (pin "2") (pinfunction "2_2") (pintype "input"))
      (node (ref "U11") (pin "3") (pinfunction "SDAA_3") (pintype "unspecified"))
    )
    (net (code "86") (name "OPP-RESET") (class "Default")
      (node (ref "U6") (pin "10") (pinfunction "B4_10") (pintype "unspecified"))
      (node (ref "U8") (pin "2") (pinfunction "1Y_2") (pintype "unspecified"))
    )
    (net (code "87") (name "OUT-00") (class "Default")
      (node (ref "DECODER-01-08") (pin "1") (pinfunction "A0_1") (pintype "unspecified"))
      (node (ref "DECODER-09-16") (pin "1") (pinfunction "A0_1") (pintype "unspecified"))
      (node (ref "DECODER-17-24") (pin "1") (pinfunction "A0_1") (pintype "unspecified"))
      (node (ref "DECODER-25-32") (pin "1") (pinfunction "A0_1") (pintype "unspecified"))
      (node (ref "U3") (pin "14") (pinfunction "(PCINT2/SS#/OC1B)PB2_14") (pintype "unspecified"))
    )
    (net (code "88") (name "OUT-01") (class "Default")
      (node (ref "DECODER-01-08") (pin "2") (pinfunction "A1_2") (pintype "unspecified"))
      (node (ref "DECODER-09-16") (pin "2") (pinfunction "A1_2") (pintype "unspecified"))
      (node (ref "DECODER-17-24") (pin "2") (pinfunction "A1_2") (pintype "unspecified"))
      (node (ref "DECODER-25-32") (pin "2") (pinfunction "A1_2") (pintype "unspecified"))
      (node (ref "U3") (pin "13") (pinfunction "(PCINT1/OC1A)PB1_13") (pintype "unspecified"))
    )
    (net (code "89") (name "OUT-02") (class "Default")
      (node (ref "DECODER-01-08") (pin "3") (pinfunction "A2_3") (pintype "unspecified"))
      (node (ref "DECODER-09-16") (pin "3") (pinfunction "A2_3") (pintype "unspecified"))
      (node (ref "DECODER-17-24") (pin "3") (pinfunction "A2_3") (pintype "unspecified"))
      (node (ref "DECODER-25-32") (pin "3") (pinfunction "A2_3") (pintype "unspecified"))
      (node (ref "U3") (pin "12") (pinfunction "(PCINT0/CLKO/ICP1)PB0_12") (pintype "unspecified"))
    )
    (net (code "90") (name "OUT-03") (class "Default")
      (node (ref "U3") (pin "11") (pinfunction "(PCINT23/AIN1)PD7_11") (pintype "unspecified"))
      (node (ref "U7") (pin "1") (pinfunction "A0_1") (pintype "unspecified"))
    )
    (net (code "91") (name "OUT-04") (class "Default")
      (node (ref "U3") (pin "10") (pinfunction "(PCINT22/OC0A/AIN0)PD6_10") (pintype "unspecified"))
      (node (ref "U7") (pin "2") (pinfunction "A1_2") (pintype "unspecified"))
    )
    (net (code "92") (name "RELAY-01") (class "Default")
      (node (ref "DECODER-01-08") (pin "15") (pinfunction "Y0#_15") (pintype "unspecified"))
      (node (ref "P1") (pin "3") (pinfunction "3_3") (pintype "unspecified"))
    )
    (net (code "93") (name "RELAY-02") (class "Default")
      (node (ref "DECODER-01-08") (pin "14") (pinfunction "Y1#_14") (pintype "unspecified"))
      (node (ref "P1") (pin "4") (pinfunction "4_4") (pintype "unspecified"))
    )
    (net (code "94") (name "RELAY-03") (class "Default")
      (node (ref "DECODER-01-08") (pin "13") (pinfunction "Y2#_13") (pintype "unspecified"))
      (node (ref "P1") (pin "5") (pinfunction "5_5") (pintype "unspecified"))
    )
    (net (code "95") (name "RELAY-04") (class "Default")
      (node (ref "DECODER-01-08") (pin "12") (pinfunction "Y3#_12") (pintype "unspecified"))
      (node (ref "P1") (pin "6") (pinfunction "6_6") (pintype "unspecified"))
    )
    (net (code "96") (name "RELAY-05") (class "Default")
      (node (ref "DECODER-01-08") (pin "11") (pinfunction "Y4#_11") (pintype "unspecified"))
      (node (ref "P1") (pin "7") (pinfunction "7_7") (pintype "unspecified"))
    )
    (net (code "97") (name "RELAY-06") (class "Default")
      (node (ref "DECODER-01-08") (pin "10") (pinfunction "Y5#_10") (pintype "unspecified"))
      (node (ref "P1") (pin "8") (pinfunction "8_8") (pintype "unspecified"))
    )
    (net (code "98") (name "RELAY-07") (class "Default")
      (node (ref "DECODER-01-08") (pin "9") (pinfunction "Y6#_9") (pintype "unspecified"))
      (node (ref "P1") (pin "9") (pinfunction "9_9") (pintype "unspecified"))
    )
    (net (code "99") (name "RELAY-08") (class "Default")
      (node (ref "DECODER-01-08") (pin "7") (pinfunction "Y7#_7") (pintype "unspecified"))
      (node (ref "P1") (pin "10") (pinfunction "10_10") (pintype "unspecified"))
    )
    (net (code "100") (name "RELAY-09") (class "Default")
      (node (ref "DECODER-09-16") (pin "15") (pinfunction "Y0#_15") (pintype "unspecified"))
      (node (ref "P2") (pin "3") (pinfunction "3_3") (pintype "unspecified"))
    )
    (net (code "101") (name "RELAY-10") (class "Default")
      (node (ref "DECODER-09-16") (pin "14") (pinfunction "Y1#_14") (pintype "unspecified"))
      (node (ref "P2") (pin "4") (pinfunction "4_4") (pintype "unspecified"))
    )
    (net (code "102") (name "RELAY-11") (class "Default")
      (node (ref "DECODER-09-16") (pin "13") (pinfunction "Y2#_13") (pintype "unspecified"))
      (node (ref "P2") (pin "5") (pinfunction "5_5") (pintype "unspecified"))
    )
    (net (code "103") (name "RELAY-12") (class "Default")
      (node (ref "DECODER-09-16") (pin "12") (pinfunction "Y3#_12") (pintype "unspecified"))
      (node (ref "P2") (pin "6") (pinfunction "6_6") (pintype "unspecified"))
    )
    (net (code "104") (name "RELAY-13") (class "Default")
      (node (ref "DECODER-09-16") (pin "11") (pinfunction "Y4#_11") (pintype "unspecified"))
      (node (ref "P2") (pin "7") (pinfunction "7_7") (pintype "unspecified"))
    )
    (net (code "105") (name "RELAY-14") (class "Default")
      (node (ref "DECODER-09-16") (pin "10") (pinfunction "Y5#_10") (pintype "unspecified"))
      (node (ref "P2") (pin "8") (pinfunction "8_8") (pintype "unspecified"))
    )
    (net (code "106") (name "RELAY-15") (class "Default")
      (node (ref "DECODER-09-16") (pin "9") (pinfunction "Y6#_9") (pintype "unspecified"))
      (node (ref "P2") (pin "9") (pinfunction "9_9") (pintype "unspecified"))
    )
    (net (code "107") (name "RELAY-16") (class "Default")
      (node (ref "DECODER-09-16") (pin "7") (pinfunction "Y7#_7") (pintype "unspecified"))
      (node (ref "P2") (pin "10") (pinfunction "10_10") (pintype "unspecified"))
    )
    (net (code "108") (name "RELAY-17") (class "Default")
      (node (ref "DECODER-17-24") (pin "15") (pinfunction "Y0#_15") (pintype "unspecified"))
      (node (ref "P3") (pin "3") (pinfunction "3_3") (pintype "unspecified"))
    )
    (net (code "109") (name "RELAY-18") (class "Default")
      (node (ref "DECODER-17-24") (pin "14") (pinfunction "Y1#_14") (pintype "unspecified"))
      (node (ref "P3") (pin "4") (pinfunction "4_4") (pintype "unspecified"))
    )
    (net (code "110") (name "RELAY-19") (class "Default")
      (node (ref "DECODER-17-24") (pin "13") (pinfunction "Y2#_13") (pintype "unspecified"))
      (node (ref "P3") (pin "5") (pinfunction "5_5") (pintype "unspecified"))
    )
    (net (code "111") (name "RELAY-20") (class "Default")
      (node (ref "DECODER-17-24") (pin "12") (pinfunction "Y3#_12") (pintype "unspecified"))
      (node (ref "P3") (pin "6") (pinfunction "6_6") (pintype "unspecified"))
    )
    (net (code "112") (name "RELAY-21") (class "Default")
      (node (ref "DECODER-17-24") (pin "11") (pinfunction "Y4#_11") (pintype "unspecified"))
      (node (ref "P3") (pin "7") (pinfunction "7_7") (pintype "unspecified"))
    )
    (net (code "113") (name "RELAY-22") (class "Default")
      (node (ref "DECODER-17-24") (pin "10") (pinfunction "Y5#_10") (pintype "unspecified"))
      (node (ref "P3") (pin "8") (pinfunction "8_8") (pintype "unspecified"))
    )
    (net (code "114") (name "RELAY-23") (class "Default")
      (node (ref "DECODER-17-24") (pin "9") (pinfunction "Y6#_9") (pintype "unspecified"))
      (node (ref "P3") (pin "9") (pinfunction "9_9") (pintype "unspecified"))
    )
    (net (code "115") (name "RELAY-24") (class "Default")
      (node (ref "DECODER-17-24") (pin "7") (pinfunction "Y7#_7") (pintype "unspecified"))
      (node (ref "P3") (pin "10") (pinfunction "10_10") (pintype "unspecified"))
    )
    (net (code "116") (name "RELAY-25") (class "Default")
      (node (ref "DECODER-25-32") (pin "15") (pinfunction "Y0#_15") (pintype "unspecified"))
      (node (ref "P4") (pin "3") (pinfunction "3_3") (pintype "unspecified"))
    )
    (net (code "117") (name "RELAY-26") (class "Default")
      (node (ref "DECODER-25-32") (pin "14") (pinfunction "Y1#_14") (pintype "unspecified"))
      (node (ref "P4") (pin "4") (pinfunction "4_4") (pintype "unspecified"))
    )
    (net (code "118") (name "RELAY-27") (class "Default")
      (node (ref "DECODER-25-32") (pin "13") (pinfunction "Y2#_13") (pintype "unspecified"))
      (node (ref "P4") (pin "5") (pinfunction "5_5") (pintype "unspecified"))
    )
    (net (code "119") (name "RELAY-28") (class "Default")
      (node (ref "DECODER-25-32") (pin "12") (pinfunction "Y3#_12") (pintype "unspecified"))
      (node (ref "P4") (pin "6") (pinfunction "6_6") (pintype "unspecified"))
    )
    (net (code "120") (name "RELAY-29") (class "Default")
      (node (ref "DECODER-25-32") (pin "11") (pinfunction "Y4#_11") (pintype "unspecified"))
      (node (ref "P4") (pin "7") (pinfunction "7_7") (pintype "unspecified"))
    )
    (net (code "121") (name "RELAY-30") (class "Default")
      (node (ref "DECODER-25-32") (pin "10") (pinfunction "Y5#_10") (pintype "unspecified"))
      (node (ref "P4") (pin "8") (pinfunction "8_8") (pintype "unspecified"))
    )
    (net (code "122") (name "RELAY-31") (class "Default")
      (node (ref "DECODER-25-32") (pin "9") (pinfunction "Y6#_9") (pintype "unspecified"))
      (node (ref "P4") (pin "9") (pinfunction "9_9") (pintype "unspecified"))
    )
    (net (code "123") (name "RELAY-32") (class "Default")
      (node (ref "DECODER-25-32") (pin "7") (pinfunction "Y7#_7") (pintype "unspecified"))
      (node (ref "P4") (pin "10") (pinfunction "10_10") (pintype "unspecified"))
    )
    (net (code "124") (name "SCL") (class "Default")
      (node (ref "RN1") (pin "1") (pinfunction "1_1") (pintype "input"))
      (node (ref "U11") (pin "7") (pinfunction "SCLB_7") (pintype "unspecified"))
      (node (ref "U3") (pin "28") (pinfunction "PC5(ADC5/SCL/PCINT13)_28") (pintype "unspecified"))
    )
    (net (code "125") (name "SD-PIN-2") (class "Default")
      (node (ref "CARD1") (pin "2") (pinfunction "CD/DAT3_2") (pintype "input"))
      (node (ref "U6") (pin "5") (pinfunction "A4_5") (pintype "unspecified"))
    )
    (net (code "126") (name "SD-PIN-3") (class "Default")
      (node (ref "CARD1") (pin "3") (pinfunction "CMD_3") (pintype "input"))
      (node (ref "U6") (pin "4") (pinfunction "A3_4") (pintype "unspecified"))
    )
    (net (code "127") (name "SD-PIN-5") (class "Default")
      (node (ref "CARD1") (pin "5") (pinfunction "CLK_5") (pintype "input"))
      (node (ref "U6") (pin "3") (pinfunction "A2_3") (pintype "unspecified"))
    )
    (net (code "128") (name "SD-PIN-7") (class "Default")
      (node (ref "CARD1") (pin "7") (pinfunction "DAT0_7") (pintype "input"))
      (node (ref "U6") (pin "2") (pinfunction "A1_2") (pintype "unspecified"))
    )
    (net (code "129") (name "SDA") (class "Default")
      (node (ref "RN1") (pin "2") (pinfunction "2_2") (pintype "input"))
      (node (ref "U11") (pin "6") (pinfunction "SDAB_6") (pintype "unspecified"))
      (node (ref "U3") (pin "27") (pinfunction "PC4(ADC4/SDA/PCINT12)_27") (pintype "unspecified"))
    )
    (net (code "130") (name "XTAL1") (class "Default")
      (node (ref "CRYSTAL-CAP-1") (pin "2") (pinfunction "2_2") (pintype "input"))
      (node (ref "U3") (pin "7") (pinfunction "(PCINT6/XTAL1/TOSC1)PB6_7") (pintype "unspecified"))
      (node (ref "X2") (pin "3") (pinfunction "OSC2_3") (pintype "unspecified"))
    )
    (net (code "131") (name "XTAL2") (class "Default")
      (node (ref "CRYSTAL-CAP-2") (pin "2") (pinfunction "2_2") (pintype "input"))
      (node (ref "U3") (pin "8") (pinfunction "(PCINT7/XTAL2/TOSC2)PB7_8") (pintype "unspecified"))
      (node (ref "X2") (pin "1") (pinfunction "OSC1_1") (pintype "unspecified"))
    )
    (net (code "132") (name "unconnected-(CARD1-CD-Pad9)") (class "Default")
      (node (ref "CARD1") (pin "9") (pinfunction "CD_9") (pintype "input+no_connect"))
    )
    (net (code "133") (name "unconnected-(CARD1-DAT1-Pad8)") (class "Default")
      (node (ref "CARD1") (pin "8") (pinfunction "DAT1_8") (pintype "input+no_connect"))
    )
    (net (code "134") (name "unconnected-(CARD1-DAT2-Pad1)") (class "Default")
      (node (ref "CARD1") (pin "1") (pinfunction "DAT2_1") (pintype "input+no_connect"))
    )
    (net (code "135") (name "unconnected-(ENCODER-01-08-EO-Pad15)") (class "Default")
      (node (ref "ENCODER-01-08") (pin "15") (pinfunction "EO_15") (pintype "unspecified+no_connect"))
    )
    (net (code "136") (name "unconnected-(U2-E-Pad9)") (class "Default")
      (node (ref "U2") (pin "9") (pinfunction "E_9") (pintype "unspecified+no_connect"))
    )
    (net (code "137") (name "unconnected-(U2-F-Pad10)") (class "Default")
      (node (ref "U2") (pin "10") (pinfunction "F_10") (pintype "unspecified+no_connect"))
    )
    (net (code "138") (name "unconnected-(U2-G-Pad11)") (class "Default")
      (node (ref "U2") (pin "11") (pinfunction "G_11") (pintype "unspecified+no_connect"))
    )
    (net (code "139") (name "unconnected-(U2-H-Pad12)") (class "Default")
      (node (ref "U2") (pin "12") (pinfunction "H_12") (pintype "unspecified+no_connect"))
    )
    (net (code "140") (name "unconnected-(U2-K=E*F*G*H-Pad13)") (class "Default")
      (node (ref "U2") (pin "13") (pinfunction "K=E*F*G*H_13") (pintype "unspecified+no_connect"))
    )
    (net (code "141") (name "unconnected-(U2-NC-Pad6)") (class "Default")
      (node (ref "U2") (pin "6") (pinfunction "NC_6") (pintype "unspecified+no_connect"))
    )
    (net (code "142") (name "unconnected-(U2-NC-Pad8)") (class "Default")
      (node (ref "U2") (pin "8") (pinfunction "NC_8") (pintype "unspecified+no_connect"))
    )
    (net (code "143") (name "unconnected-(U3-ADC6-Pad19)") (class "Default")
      (node (ref "U3") (pin "19") (pinfunction "ADC6_19") (pintype "unspecified+no_connect"))
    )
    (net (code "144") (name "unconnected-(U3-ADC7-Pad22)") (class "Default")
      (node (ref "U3") (pin "22") (pinfunction "ADC7_22") (pintype "unspecified+no_connect"))
    )
    (net (code "145") (name "unconnected-(U4-NC-Pad6)") (class "Default")
      (node (ref "U4") (pin "6") (pinfunction "NC_6") (pintype "unspecified+no_connect"))
    )
    (net (code "146") (name "unconnected-(U4-NC-Pad8)") (class "Default")
      (node (ref "U4") (pin "8") (pinfunction "NC_8") (pintype "unspecified+no_connect"))
    )
    (net (code "147") (name "unconnected-(U6-NC-Pad6)") (class "Default")
      (node (ref "U6") (pin "6") (pinfunction "NC_6") (pintype "unspecified+no_connect"))
    )
    (net (code "148") (name "unconnected-(U6-NC-Pad9)") (class "Default")
      (node (ref "U6") (pin "9") (pinfunction "NC_9") (pintype "unspecified+no_connect"))
    )
    (net (code "149") (name "unconnected-(U7-Y4#-Pad11)") (class "Default")
      (node (ref "U7") (pin "11") (pinfunction "Y4#_11") (pintype "unspecified+no_connect"))
    )
    (net (code "150") (name "unconnected-(U7-Y5#-Pad10)") (class "Default")
      (node (ref "U7") (pin "10") (pinfunction "Y5#_10") (pintype "unspecified+no_connect"))
    )
    (net (code "151") (name "unconnected-(U7-Y6#-Pad9)") (class "Default")
      (node (ref "U7") (pin "9") (pinfunction "Y6#_9") (pintype "unspecified+no_connect"))
    )
    (net (code "152") (name "unconnected-(U7-Y7#-Pad7)") (class "Default")
      (node (ref "U7") (pin "7") (pinfunction "Y7#_7") (pintype "unspecified+no_connect"))
    )
    (net (code "153") (name "unconnected-(U8-2A-Pad3)") (class "Default")
      (node (ref "U8") (pin "3") (pinfunction "2A_3") (pintype "unspecified+no_connect"))
    )
    (net (code "154") (name "unconnected-(U8-2Y-Pad4)") (class "Default")
      (node (ref "U8") (pin "4") (pinfunction "2Y_4") (pintype "unspecified+no_connect"))
    )
    (net (code "155") (name "unconnected-(U8-3A-Pad5)") (class "Default")
      (node (ref "U8") (pin "5") (pinfunction "3A_5") (pintype "unspecified+no_connect"))
    )
    (net (code "156") (name "unconnected-(U8-3Y-Pad6)") (class "Default")
      (node (ref "U8") (pin "6") (pinfunction "3Y_6") (pintype "unspecified+no_connect"))
    )
    (net (code "157") (name "unconnected-(U8-4A-Pad9)") (class "Default")
      (node (ref "U8") (pin "9") (pinfunction "4A_9") (pintype "unspecified+no_connect"))
    )
    (net (code "158") (name "unconnected-(U8-4Y-Pad8)") (class "Default")
      (node (ref "U8") (pin "8") (pinfunction "4Y_8") (pintype "unspecified+no_connect"))
    )
    (net (code "159") (name "unconnected-(U8-5A-Pad11)") (class "Default")
      (node (ref "U8") (pin "11") (pinfunction "5A_11") (pintype "unspecified+no_connect"))
    )
    (net (code "160") (name "unconnected-(U8-5Y-Pad10)") (class "Default")
      (node (ref "U8") (pin "10") (pinfunction "5Y_10") (pintype "unspecified+no_connect"))
    )
    (net (code "161") (name "unconnected-(U8-6A-Pad13)") (class "Default")
      (node (ref "U8") (pin "13") (pinfunction "6A_13") (pintype "unspecified+no_connect"))
    )
    (net (code "162") (name "unconnected-(U8-6Y-Pad12)") (class "Default")
      (node (ref "U8") (pin "12") (pinfunction "6Y_12") (pintype "unspecified+no_connect"))
    )
    (net (code "163") (name "unconnected-(U10-A2-Pad6)") (class "Default")
      (node (ref "U10") (pin "6") (pinfunction "A2_6") (pintype "unspecified+no_connect"))
    )
    (net (code "164") (name "unconnected-(U10-EO-Pad15)") (class "Default")
      (node (ref "U10") (pin "15") (pinfunction "EO_15") (pintype "unspecified+no_connect"))
    )
    (net (code "165") (name "unconnected-(U12-2B-Pad2)") (class "Default")
      (node (ref "U12") (pin "2") (pinfunction "2B_2") (pintype "unspecified+no_connect"))
    )
    (net (code "166") (name "unconnected-(U12-2C-Pad15)") (class "Default")
      (node (ref "U12") (pin "15") (pinfunction "2C_15") (pintype "unspecified+no_connect"))
    )
    (net (code "167") (name "unconnected-(U12-3B-Pad3)") (class "Default")
      (node (ref "U12") (pin "3") (pinfunction "3B_3") (pintype "unspecified+no_connect"))
    )
    (net (code "168") (name "unconnected-(U12-3C-Pad14)") (class "Default")
      (node (ref "U12") (pin "14") (pinfunction "3C_14") (pintype "unspecified+no_connect"))
    )
    (net (code "169") (name "unconnected-(U12-4B-Pad4)") (class "Default")
      (node (ref "U12") (pin "4") (pinfunction "4B_4") (pintype "unspecified+no_connect"))
    )
    (net (code "170") (name "unconnected-(U12-4C-Pad13)") (class "Default")
      (node (ref "U12") (pin "13") (pinfunction "4C_13") (pintype "unspecified+no_connect"))
    )
    (net (code "171") (name "unconnected-(U12-6B-Pad6)") (class "Default")
      (node (ref "U12") (pin "6") (pinfunction "6B_6") (pintype "unspecified+no_connect"))
    )
    (net (code "172") (name "unconnected-(U12-6C-Pad11)") (class "Default")
      (node (ref "U12") (pin "11") (pinfunction "6C_11") (pintype "unspecified+no_connect"))
    )
    (net (code "173") (name "unconnected-(U12-7B-Pad7)") (class "Default")
      (node (ref "U12") (pin "7") (pinfunction "7B_7") (pintype "unspecified+no_connect"))
    )
    (net (code "174") (name "unconnected-(U12-7C-Pad10)") (class "Default")
      (node (ref "U12") (pin "10") (pinfunction "7C_10") (pintype "unspecified+no_connect"))
    )
    (net (code "175") (name "unconnected-(U12-COM-Pad9)") (class "Default")
      (node (ref "U12") (pin "9") (pinfunction "COM_9") (pintype "unspecified+no_connect"))
    )
  )
)
